# videobrick_alpha4.net
KiCad netlist of a schematic drawn in EAGLE
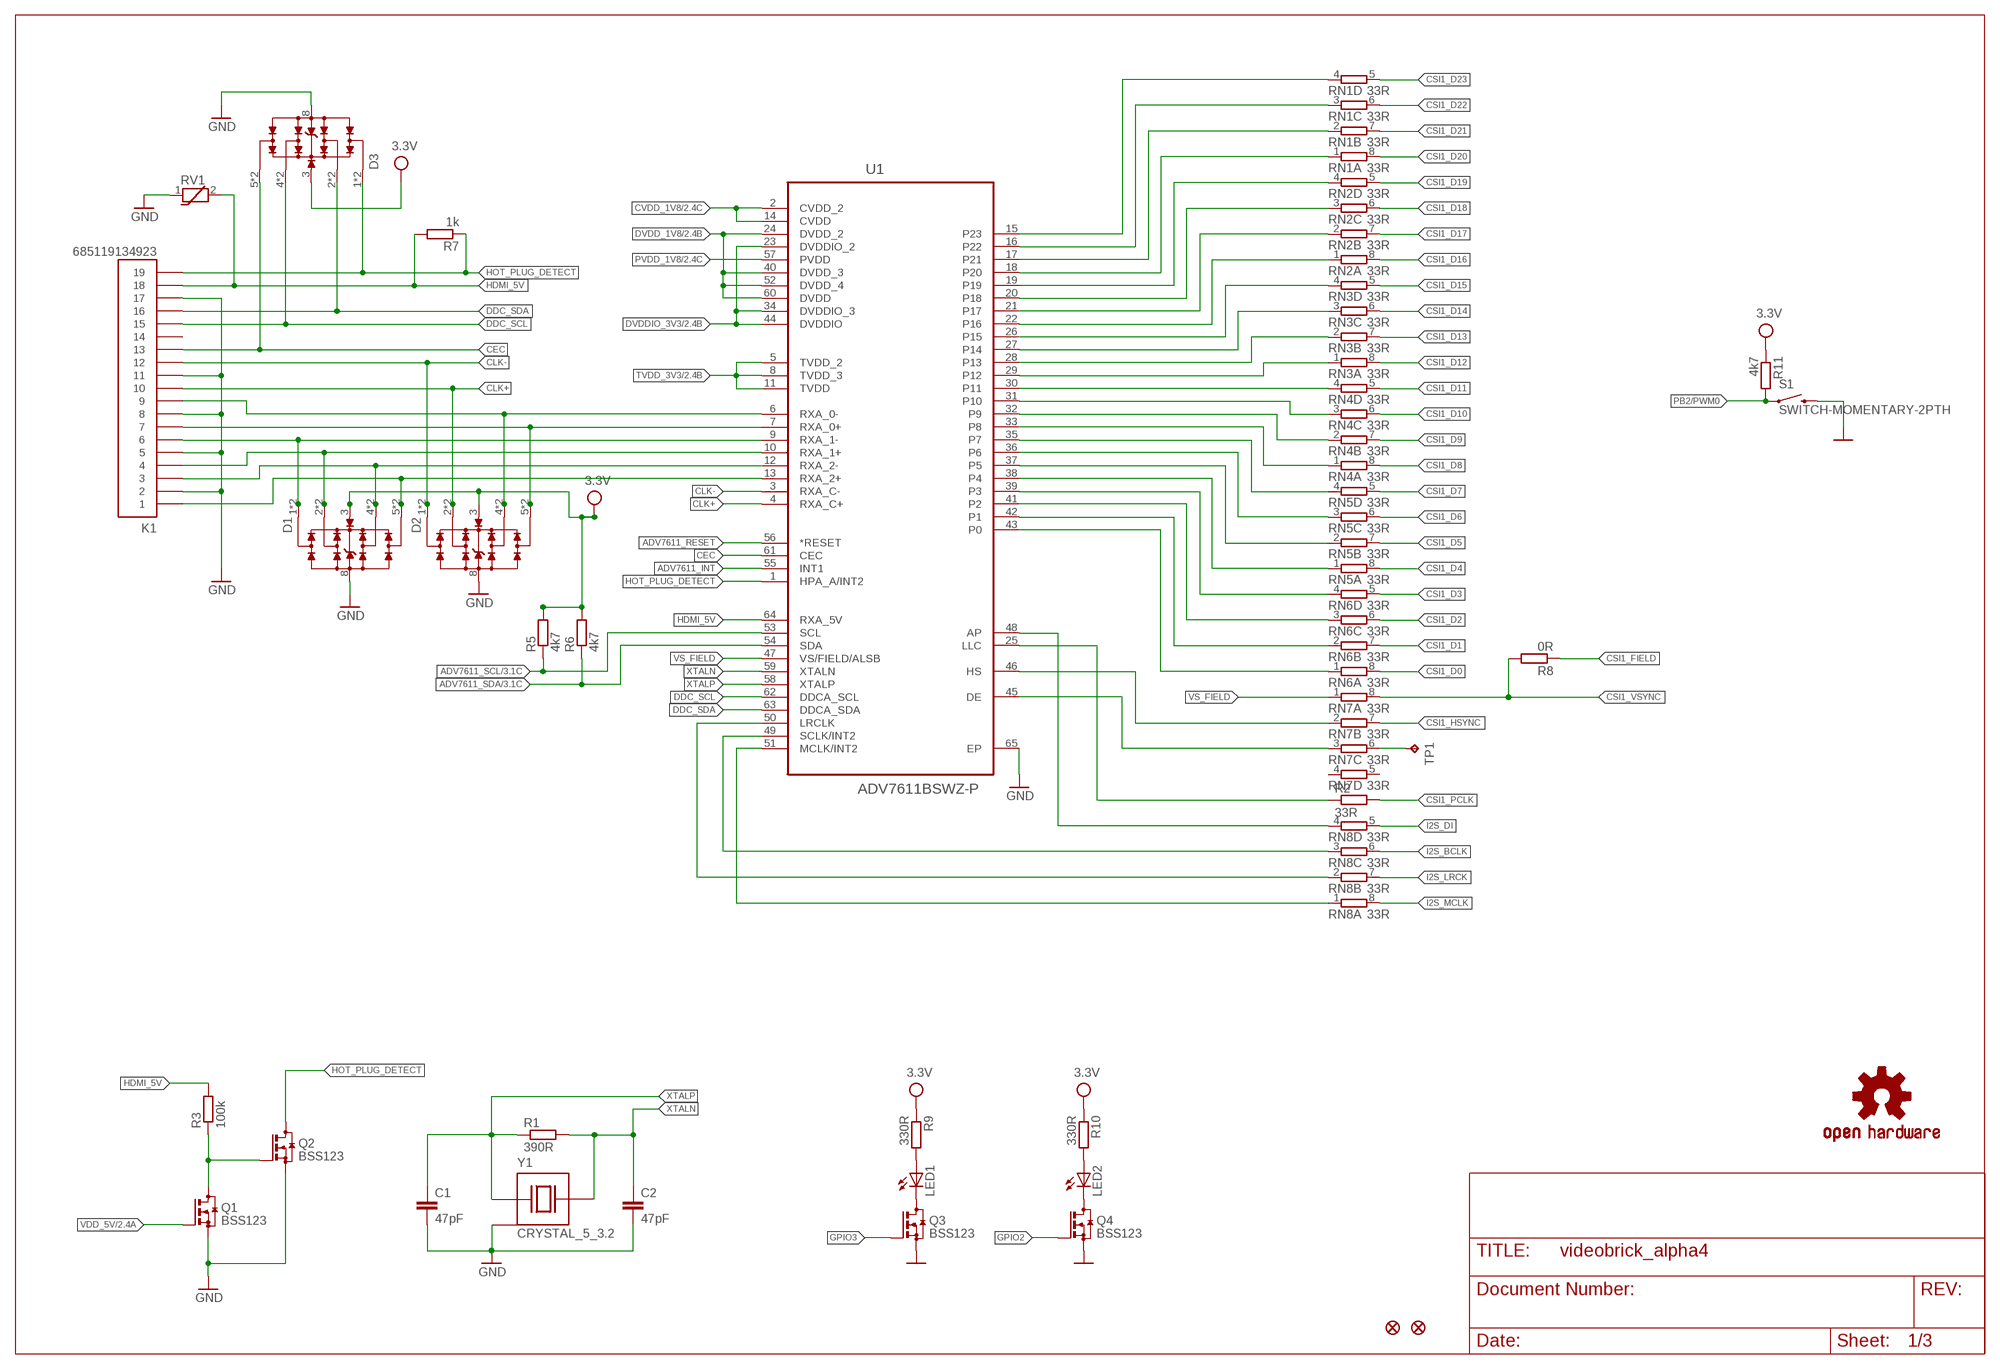
[diagram p0: schematic, sheet 1]
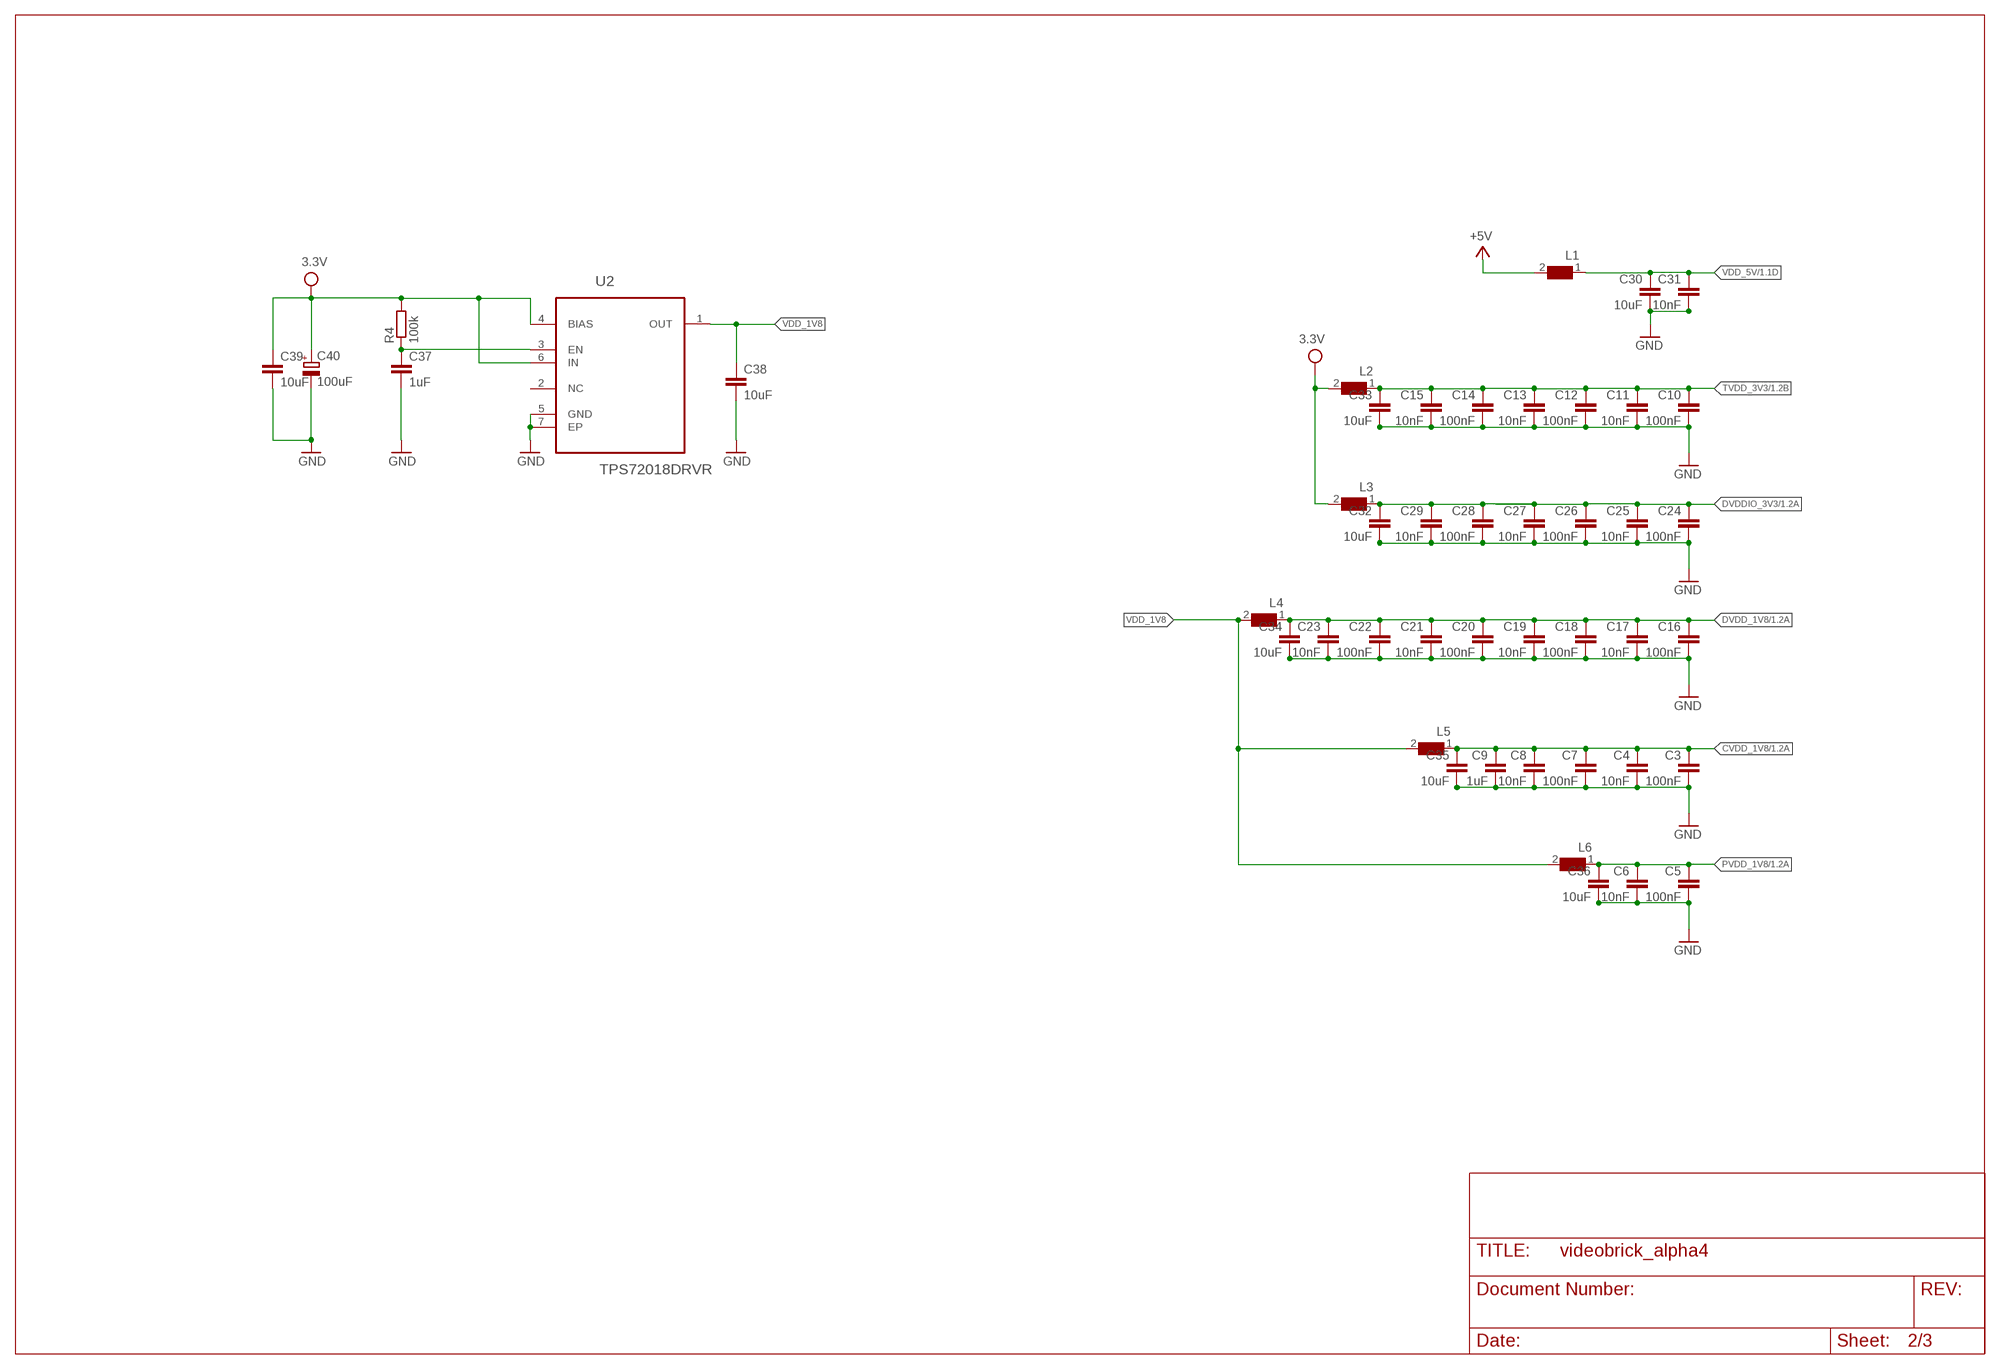
[diagram p1: schematic, sheet 2]
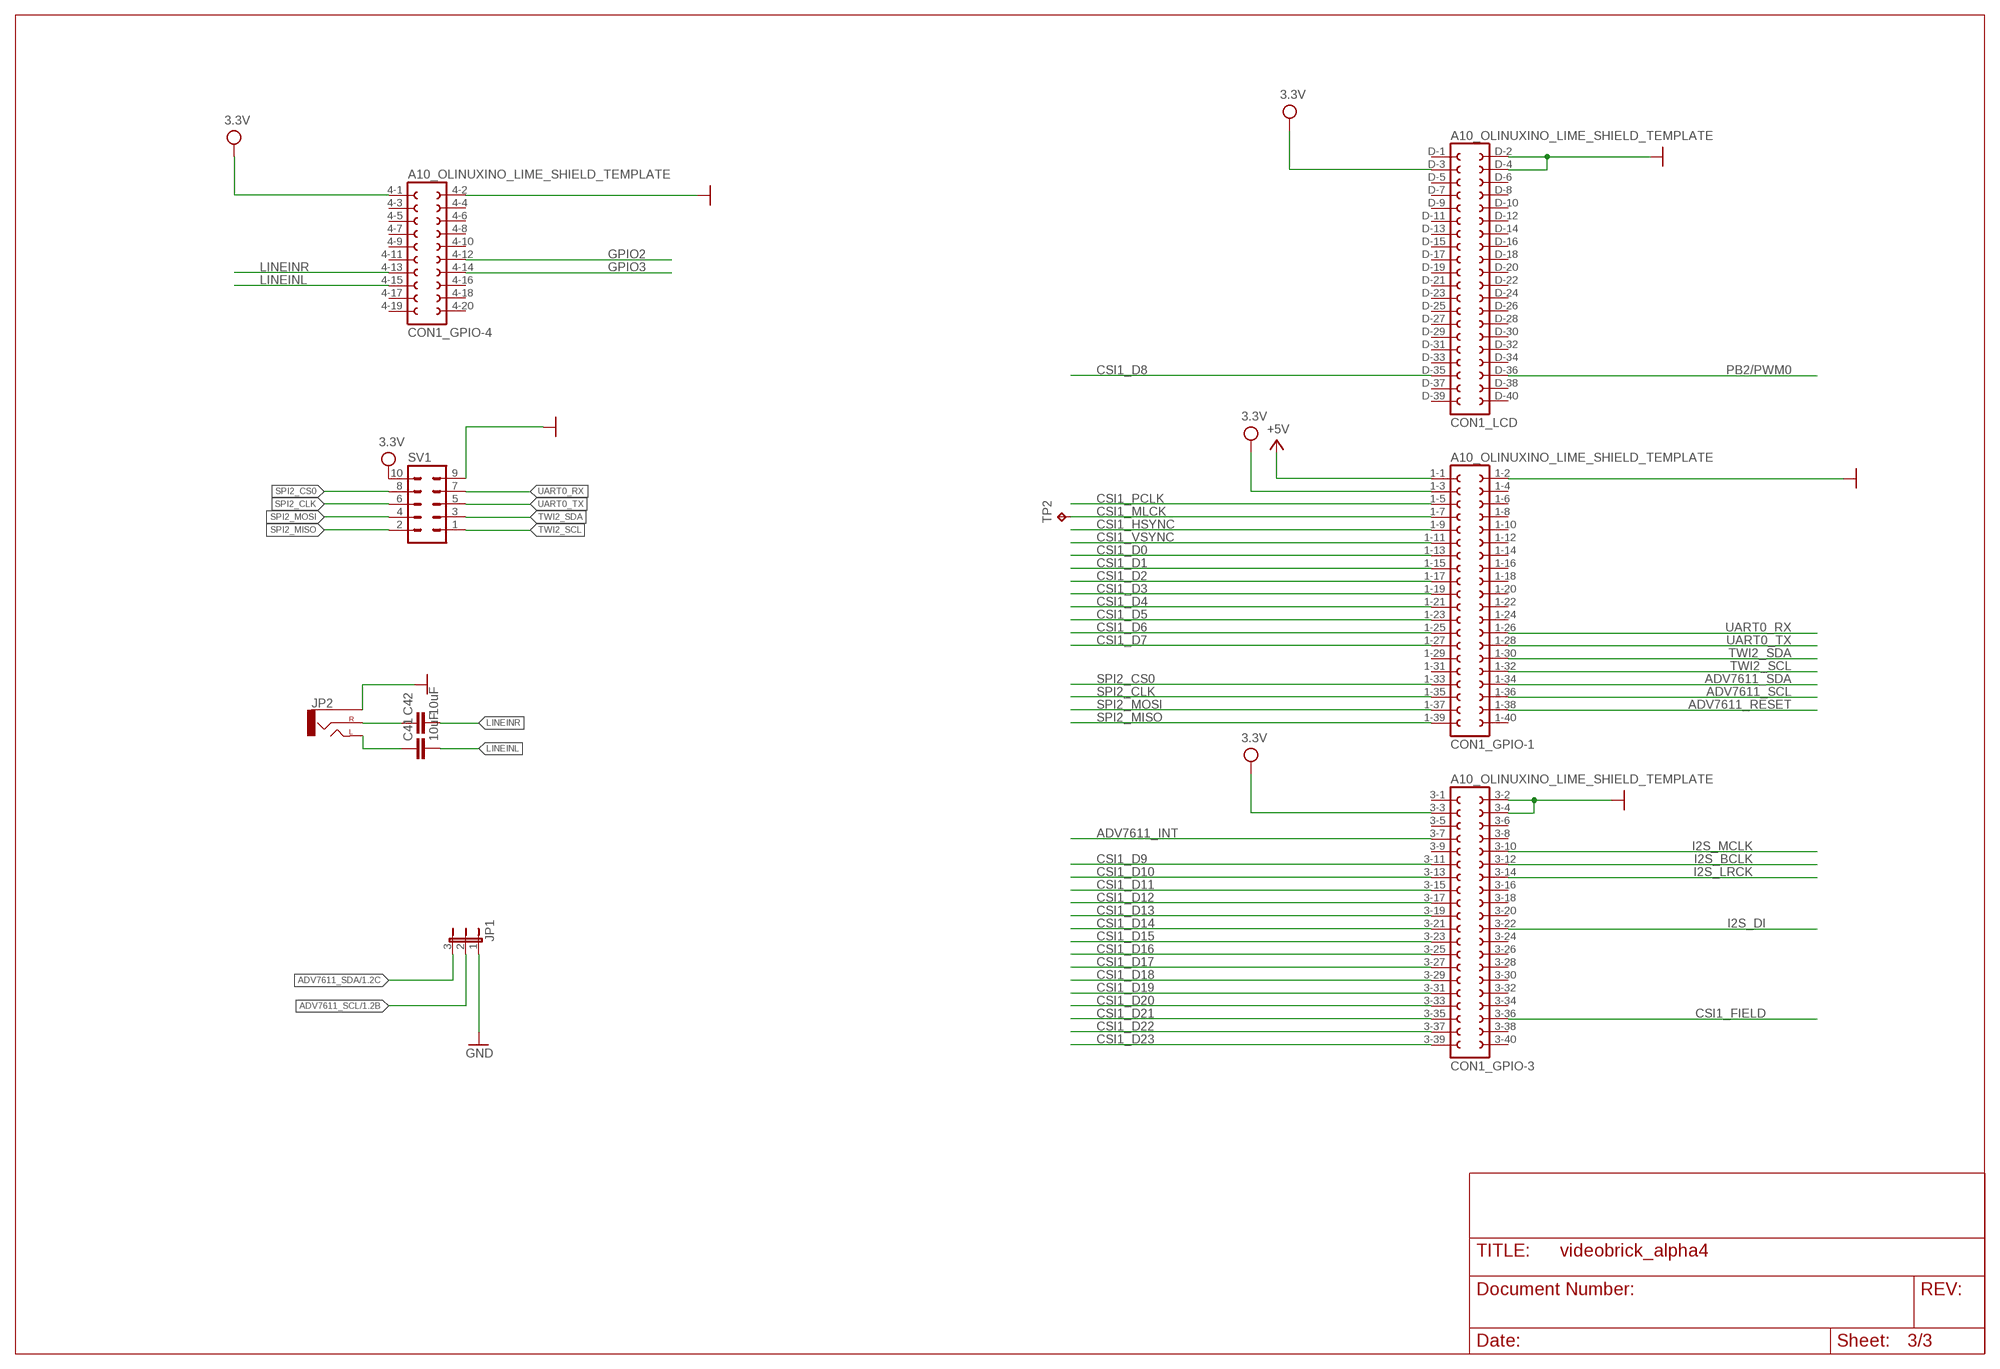
[diagram p2: schematic, sheet 3]

(export (version "E")
  (design (tool "Eeschema 10.0.6"))
  (components
    (comp (ref "C1")
      (value "47pF")
      (footprint "eagle-import:C0402")
      (libsource (lib "eagle-import") (part "C-EUC0402"))
    )
    (comp (ref "C2")
      (value "47pF")
      (footprint "eagle-import:C0402")
      (libsource (lib "eagle-import") (part "C-EUC0402"))
    )
    (comp (ref "D1")
      (value "WE-TVS_82401444")
      (footprint "eagle-import:WE-TVS_MSOP-10L")
      (fields (field (name "MPN") "82401444"))
      (libsource (lib "eagle-import") (part "WE-TVS_82401444"))
    )
    (comp (ref "D2")
      (value "WE-TVS_82401444")
      (footprint "eagle-import:WE-TVS_MSOP-10L")
      (fields (field (name "MPN") "82401444"))
      (libsource (lib "eagle-import") (part "WE-TVS_82401444"))
    )
    (comp (ref "D3")
      (value "WE-TVS_82401444")
      (footprint "eagle-import:WE-TVS_MSOP-10L")
      (fields (field (name "MPN") "82401444"))
      (libsource (lib "eagle-import") (part "WE-TVS_82401444"))
    )
    (comp (ref "FID1")
      (value "FIDUCIALUFIDUCIAL")
      (footprint "eagle-import:MICRO-FIDUCIAL")
      (libsource (lib "eagle-import") (part "FIDUCIALUFIDUCIAL"))
    )
    (comp (ref "FID2")
      (value "FIDUCIAL1X2")
      (footprint "eagle-import:FIDUCIAL-1X2")
      (libsource (lib "eagle-import") (part "FIDUCIAL1X2"))
    )
    (comp (ref "K1")
      (value "685119134923")
      (footprint "eagle-import:685119134923")
      (libsource (lib "eagle-import") (part "685119134923"))
    )
    (comp (ref "LED1")
      (value "LEDCHIPLED_0805")
      (footprint "eagle-import:CHIPLED_0805")
      (libsource (lib "eagle-import") (part "LEDCHIPLED_0805"))
    )
    (comp (ref "LED2")
      (value "LEDCHIPLED_0805")
      (footprint "eagle-import:CHIPLED_0805")
      (libsource (lib "eagle-import") (part "LEDCHIPLED_0805"))
    )
    (comp (ref "LOGO1")
      (value "OSHW-LOGOL")
      (footprint "eagle-import:OSHW-LOGO-L")
      (libsource (lib "eagle-import") (part "OSHW-LOGOL"))
    )
    (comp (ref "Q1")
      (value "BSS123")
      (footprint "eagle-import:SOT23")
      (libsource (lib "eagle-import") (part "BSS123"))
    )
    (comp (ref "Q2")
      (value "BSS123")
      (footprint "eagle-import:SOT23")
      (libsource (lib "eagle-import") (part "BSS123"))
    )
    (comp (ref "Q3")
      (value "BSS123")
      (footprint "eagle-import:SOT23")
      (libsource (lib "eagle-import") (part "BSS123"))
    )
    (comp (ref "Q4")
      (value "BSS123")
      (footprint "eagle-import:SOT23")
      (libsource (lib "eagle-import") (part "BSS123"))
    )
    (comp (ref "R1")
      (value "390R")
      (footprint "eagle-import:R0402")
      (libsource (lib "eagle-import") (part "R-EU_R0402"))
    )
    (comp (ref "R2")
      (value "33R")
      (footprint "eagle-import:R0402")
      (libsource (lib "eagle-import") (part "R-EU_R0402"))
    )
    (comp (ref "R3")
      (value "100k")
      (footprint "eagle-import:R0402")
      (libsource (lib "eagle-import") (part "R-EU_R0402"))
    )
    (comp (ref "R5")
      (value "4k7")
      (footprint "eagle-import:R0402")
      (libsource (lib "eagle-import") (part "R-EU_R0402"))
    )
    (comp (ref "R6")
      (value "4k7")
      (footprint "eagle-import:R0402")
      (libsource (lib "eagle-import") (part "R-EU_R0402"))
    )
    (comp (ref "R7")
      (value "1k")
      (footprint "eagle-import:R0402")
      (libsource (lib "eagle-import") (part "R-EU_R0402"))
    )
    (comp (ref "R8")
      (value "0R")
      (footprint "eagle-import:R0402")
      (libsource (lib "eagle-import") (part "R-EU_R0402"))
    )
    (comp (ref "R9")
      (value "330R")
      (footprint "eagle-import:R0402")
      (libsource (lib "eagle-import") (part "R-EU_R0402"))
    )
    (comp (ref "R10")
      (value "330R")
      (footprint "eagle-import:R0402")
      (libsource (lib "eagle-import") (part "R-EU_R0402"))
    )
    (comp (ref "R11")
      (value "4k7")
      (footprint "eagle-import:R0402")
      (libsource (lib "eagle-import") (part "R-EU_R0402"))
    )
    (comp (ref "RN1")
      (value "33R")
      (footprint "eagle-import:4X0402ARV341")
      (libsource (lib "eagle-import") (part "4R-N0402ARV341"))
    )
    (comp (ref "RN2")
      (value "33R")
      (footprint "eagle-import:4X0402ARV341")
      (libsource (lib "eagle-import") (part "4R-N0402ARV341"))
    )
    (comp (ref "RN3")
      (value "33R")
      (footprint "eagle-import:4X0402ARV341")
      (libsource (lib "eagle-import") (part "4R-N0402ARV341"))
    )
    (comp (ref "RN4")
      (value "33R")
      (footprint "eagle-import:4X0402ARV341")
      (libsource (lib "eagle-import") (part "4R-N0402ARV341"))
    )
    (comp (ref "RN5")
      (value "33R")
      (footprint "eagle-import:4X0402ARV341")
      (libsource (lib "eagle-import") (part "4R-N0402ARV341"))
    )
    (comp (ref "RN6")
      (value "33R")
      (footprint "eagle-import:4X0402ARV341")
      (libsource (lib "eagle-import") (part "4R-N0402ARV341"))
    )
    (comp (ref "RN7")
      (value "33R")
      (footprint "eagle-import:4X0402ARV341")
      (libsource (lib "eagle-import") (part "4R-N0402ARV341"))
    )
    (comp (ref "RN8")
      (value "33R")
      (footprint "eagle-import:4X0402ARV341")
      (libsource (lib "eagle-import") (part "4R-N0402ARV341"))
    )
    (comp (ref "RV1")
      (value "WE-VS-82537040_0402")
      (footprint "eagle-import:WESURGE_0402")
      (fields (field (name "MPN") "82537040"))
      (libsource (lib "eagle-import") (part "WE-VS_0402-82537040"))
    )
    (comp (ref "S1")
      (value "SWITCH-MOMENTARY-2PTH")
      (footprint "eagle-import:TACTILE-PTH")
      (libsource (lib "eagle-import") (part "SWITCH-MOMENTARY-2PTH"))
    )
    (comp (ref "TP1")
      (value "TPTP06R")
      (footprint "eagle-import:TP06R")
      (libsource (lib "eagle-import") (part "TPTP06R"))
    )
    (comp (ref "U1")
      (value "ADV7611BSWZ-P")
      (footprint "eagle-import:QFP50P1200X1200X160-65N")
      (libsource (lib "eagle-import") (part "ADV7611BSWZ-P"))
    )
    (comp (ref "Y1")
      (value "CRYSTAL_5_3.2")
      (footprint "eagle-import:5MM_3.2MM")
      (libsource (lib "eagle-import") (part "CRYSTAL_5_3.2"))
    )
    (comp (ref "C41")
      (value "10uF")
      (footprint "eagle-import:C0805")
      (libsource (lib "eagle-import") (part "C-EUC0805"))
    )
    (comp (ref "C42")
      (value "10uF")
      (footprint "eagle-import:C0805")
      (libsource (lib "eagle-import") (part "C-EUC0805"))
    )
    (comp (ref "CON1")
      (value "A10_OLINUXINO_LIME_SHIELD_TEMPLATE")
      (footprint "eagle-import:A10_OLINUXINO_LIME_SHIELD")
      (libsource (lib "eagle-import") (part "A10_OLINUXINO_LIME_SHIELD_TEMPLATE"))
    )
    (comp (ref "JP1")
      (value "JP2E")
      (footprint "eagle-import:JP2")
      (libsource (lib "eagle-import") (part "JP2E"))
    )
    (comp (ref "JP2")
      (value "AUDIO-JACKPTH")
      (footprint "eagle-import:AUDIO-JACK")
      (libsource (lib "eagle-import") (part "AUDIO-JACKPTH"))
    )
    (comp (ref "SV1")
      (value "MA05-2")
      (footprint "eagle-import:MA05-2")
      (libsource (lib "eagle-import") (part "MA05-2"))
    )
    (comp (ref "TP2")
      (value "TPTP06R")
      (footprint "eagle-import:TP06R")
      (libsource (lib "eagle-import") (part "TPTP06R"))
    )
    (comp (ref "C3")
      (value "100nF")
      (footprint "eagle-import:C0402")
      (libsource (lib "eagle-import") (part "C-EUC0402"))
    )
    (comp (ref "C4")
      (value "10nF")
      (footprint "eagle-import:C0402")
      (libsource (lib "eagle-import") (part "C-EUC0402"))
    )
    (comp (ref "C5")
      (value "100nF")
      (footprint "eagle-import:C0402")
      (libsource (lib "eagle-import") (part "C-EUC0402"))
    )
    (comp (ref "C6")
      (value "10nF")
      (footprint "eagle-import:C0402")
      (libsource (lib "eagle-import") (part "C-EUC0402"))
    )
    (comp (ref "C7")
      (value "100nF")
      (footprint "eagle-import:C0402")
      (libsource (lib "eagle-import") (part "C-EUC0402"))
    )
    (comp (ref "C8")
      (value "10nF")
      (footprint "eagle-import:C0402")
      (libsource (lib "eagle-import") (part "C-EUC0402"))
    )
    (comp (ref "C9")
      (value "1uF")
      (footprint "eagle-import:C0603")
      (libsource (lib "eagle-import") (part "C-EUC0603"))
    )
    (comp (ref "C10")
      (value "100nF")
      (footprint "eagle-import:C0402")
      (libsource (lib "eagle-import") (part "C-EUC0402"))
    )
    (comp (ref "C11")
      (value "10nF")
      (footprint "eagle-import:C0402")
      (libsource (lib "eagle-import") (part "C-EUC0402"))
    )
    (comp (ref "C12")
      (value "100nF")
      (footprint "eagle-import:C0402")
      (libsource (lib "eagle-import") (part "C-EUC0402"))
    )
    (comp (ref "C13")
      (value "10nF")
      (footprint "eagle-import:C0402")
      (libsource (lib "eagle-import") (part "C-EUC0402"))
    )
    (comp (ref "C14")
      (value "100nF")
      (footprint "eagle-import:C0402")
      (libsource (lib "eagle-import") (part "C-EUC0402"))
    )
    (comp (ref "C15")
      (value "10nF")
      (footprint "eagle-import:C0402")
      (libsource (lib "eagle-import") (part "C-EUC0402"))
    )
    (comp (ref "C16")
      (value "100nF")
      (footprint "eagle-import:C0402")
      (libsource (lib "eagle-import") (part "C-EUC0402"))
    )
    (comp (ref "C17")
      (value "10nF")
      (footprint "eagle-import:C0402")
      (libsource (lib "eagle-import") (part "C-EUC0402"))
    )
    (comp (ref "C18")
      (value "100nF")
      (footprint "eagle-import:C0402")
      (libsource (lib "eagle-import") (part "C-EUC0402"))
    )
    (comp (ref "C19")
      (value "10nF")
      (footprint "eagle-import:C0402")
      (libsource (lib "eagle-import") (part "C-EUC0402"))
    )
    (comp (ref "C20")
      (value "100nF")
      (footprint "eagle-import:C0402")
      (libsource (lib "eagle-import") (part "C-EUC0402"))
    )
    (comp (ref "C21")
      (value "10nF")
      (footprint "eagle-import:C0402")
      (libsource (lib "eagle-import") (part "C-EUC0402"))
    )
    (comp (ref "C22")
      (value "100nF")
      (footprint "eagle-import:C0402")
      (libsource (lib "eagle-import") (part "C-EUC0402"))
    )
    (comp (ref "C23")
      (value "10nF")
      (footprint "eagle-import:C0402")
      (libsource (lib "eagle-import") (part "C-EUC0402"))
    )
    (comp (ref "C24")
      (value "100nF")
      (footprint "eagle-import:C0402")
      (libsource (lib "eagle-import") (part "C-EUC0402"))
    )
    (comp (ref "C25")
      (value "10nF")
      (footprint "eagle-import:C0402")
      (libsource (lib "eagle-import") (part "C-EUC0402"))
    )
    (comp (ref "C26")
      (value "100nF")
      (footprint "eagle-import:C0402")
      (libsource (lib "eagle-import") (part "C-EUC0402"))
    )
    (comp (ref "C27")
      (value "10nF")
      (footprint "eagle-import:C0402")
      (libsource (lib "eagle-import") (part "C-EUC0402"))
    )
    (comp (ref "C28")
      (value "100nF")
      (footprint "eagle-import:C0402")
      (libsource (lib "eagle-import") (part "C-EUC0402"))
    )
    (comp (ref "C29")
      (value "10nF")
      (footprint "eagle-import:C0402")
      (libsource (lib "eagle-import") (part "C-EUC0402"))
    )
    (comp (ref "C30")
      (value "10uF")
      (footprint "eagle-import:C0805")
      (libsource (lib "eagle-import") (part "C-EUC0805"))
    )
    (comp (ref "C31")
      (value "10nF")
      (footprint "eagle-import:C0402")
      (libsource (lib "eagle-import") (part "C-EUC0402"))
    )
    (comp (ref "C32")
      (value "10uF")
      (footprint "eagle-import:C0805")
      (libsource (lib "eagle-import") (part "C-EUC0805"))
    )
    (comp (ref "C33")
      (value "10uF")
      (footprint "eagle-import:C0805")
      (libsource (lib "eagle-import") (part "C-EUC0805"))
    )
    (comp (ref "C34")
      (value "10uF")
      (footprint "eagle-import:C0805")
      (libsource (lib "eagle-import") (part "C-EUC0805"))
    )
    (comp (ref "C35")
      (value "10uF")
      (footprint "eagle-import:C0805")
      (libsource (lib "eagle-import") (part "C-EUC0805"))
    )
    (comp (ref "C36")
      (value "10uF")
      (footprint "eagle-import:C0805")
      (libsource (lib "eagle-import") (part "C-EUC0805"))
    )
    (comp (ref "C37")
      (value "1uF")
      (footprint "eagle-import:C0603")
      (libsource (lib "eagle-import") (part "C-EUC0603"))
    )
    (comp (ref "C38")
      (value "10uF")
      (footprint "eagle-import:C0805")
      (libsource (lib "eagle-import") (part "C-EUC0805"))
    )
    (comp (ref "C39")
      (value "10uF")
      (footprint "eagle-import:C0805")
      (libsource (lib "eagle-import") (part "C-EUC0805"))
    )
    (comp (ref "C40")
      (value "100uF")
      (footprint "eagle-import:153CLV-0405")
      (libsource (lib "eagle-import") (part "CPOL-EU153CLV-0405"))
    )
    (comp (ref "L1")
      (value "WE-CBF-742792040_0805")
      (footprint "eagle-import:0805")
      (fields (field (name "MPN") "742792040"))
      (libsource (lib "eagle-import") (part "WE-CBF_0805-742792040"))
    )
    (comp (ref "L2")
      (value "WE-CBF-742792040_0805")
      (footprint "eagle-import:0805")
      (fields (field (name "MPN") "742792040"))
      (libsource (lib "eagle-import") (part "WE-CBF_0805-742792040"))
    )
    (comp (ref "L3")
      (value "WE-CBF-742792040_0805")
      (footprint "eagle-import:0805")
      (fields (field (name "MPN") "742792040"))
      (libsource (lib "eagle-import") (part "WE-CBF_0805-742792040"))
    )
    (comp (ref "L4")
      (value "WE-CBF-742792040_0805")
      (footprint "eagle-import:0805")
      (fields (field (name "MPN") "742792040"))
      (libsource (lib "eagle-import") (part "WE-CBF_0805-742792040"))
    )
    (comp (ref "L5")
      (value "WE-CBF-742792040_0805")
      (footprint "eagle-import:0805")
      (fields (field (name "MPN") "742792040"))
      (libsource (lib "eagle-import") (part "WE-CBF_0805-742792040"))
    )
    (comp (ref "L6")
      (value "WE-CBF-742792040_0805")
      (footprint "eagle-import:0805")
      (fields (field (name "MPN") "742792040"))
      (libsource (lib "eagle-import") (part "WE-CBF_0805-742792040"))
    )
    (comp (ref "R4")
      (value "100k")
      (footprint "eagle-import:R0402")
      (libsource (lib "eagle-import") (part "R-EU_R0402"))
    )
    (comp (ref "U2")
      (value "TPS72018DRVR")
      (footprint "eagle-import:SON65P200X200X80-7N")
      (libsource (lib "eagle-import") (part "TPS72018DRVR"))
    )
  )
  (nets
    (net (code "1") (name "+5V") (class "Default")
      (node (ref "CON1") (pin "1-1") (pinfunction "1_1-1") (pintype "passive"))
      (node (ref "L1") (pin "2") (pinfunction "2_2") (pintype "passive"))
    )
    (net (code "2") (name "ADV7611_INT") (class "Default")
      (node (ref "CON1") (pin "3-7") (pinfunction "7_3-7") (pintype "passive"))
      (node (ref "U1") (pin "55") (pinfunction "INT1_55") (pintype "input"))
    )
    (net (code "3") (name "ADV7611_RESET") (class "Default")
      (node (ref "CON1") (pin "1-38") (pinfunction "38_1-38") (pintype "passive"))
      (node (ref "U1") (pin "56") (pinfunction "*RESET_56") (pintype "input"))
    )
    (net (code "4") (name "ADV7611_SCL") (class "Default")
      (node (ref "CON1") (pin "1-36") (pinfunction "36_1-36") (pintype "passive"))
      (node (ref "JP1") (pin "2") (pinfunction "2_2") (pintype "passive"))
      (node (ref "R5") (pin "1") (pinfunction "1_1") (pintype "passive"))
      (node (ref "U1") (pin "53") (pinfunction "SCL_53") (pintype "input"))
    )
    (net (code "5") (name "ADV7611_SDA") (class "Default")
      (node (ref "CON1") (pin "1-34") (pinfunction "34_1-34") (pintype "passive"))
      (node (ref "JP1") (pin "3") (pinfunction "3_3") (pintype "passive"))
      (node (ref "R6") (pin "1") (pinfunction "1_1") (pintype "passive"))
      (node (ref "U1") (pin "54") (pinfunction "SDA_54") (pintype "bidirectional"))
    )
    (net (code "6") (name "CEC") (class "Default")
      (node (ref "D3") (pin "5") (pinfunction "4_5") (pintype "passive"))
      (node (ref "D3") (pin "6") (pinfunction "4_6") (pintype "passive"))
      (node (ref "K1") (pin "13") (pinfunction "13_13") (pintype "passive"))
      (node (ref "U1") (pin "61") (pinfunction "CEC_61") (pintype "input"))
    )
    (net (code "7") (name "CLK+") (class "Default")
      (node (ref "D2") (pin "2") (pinfunction "2_2") (pintype "passive"))
      (node (ref "D2") (pin "9") (pinfunction "2_9") (pintype "passive"))
      (node (ref "K1") (pin "10") (pinfunction "10_10") (pintype "passive"))
      (node (ref "U1") (pin "4") (pinfunction "RXA_C+_4") (pintype "input"))
    )
    (net (code "8") (name "CLK-") (class "Default")
      (node (ref "D2") (pin "1") (pinfunction "1_1") (pintype "passive"))
      (node (ref "D2") (pin "10") (pinfunction "1_10") (pintype "passive"))
      (node (ref "K1") (pin "12") (pinfunction "12_12") (pintype "passive"))
      (node (ref "U1") (pin "3") (pinfunction "RXA_C-_3") (pintype "input"))
    )
    (net (code "9") (name "CSI1_D0") (class "Default")
      (node (ref "CON1") (pin "1-13") (pinfunction "13_1-13") (pintype "passive"))
      (node (ref "RN6") (pin "8") (pinfunction "2_8") (pintype "passive"))
    )
    (net (code "10") (name "CSI1_D1") (class "Default")
      (node (ref "CON1") (pin "1-15") (pinfunction "15_1-15") (pintype "passive"))
      (node (ref "RN6") (pin "7") (pinfunction "2_7") (pintype "passive"))
    )
    (net (code "11") (name "CSI1_D2") (class "Default")
      (node (ref "CON1") (pin "1-17") (pinfunction "17_1-17") (pintype "passive"))
      (node (ref "RN6") (pin "6") (pinfunction "2_6") (pintype "passive"))
    )
    (net (code "12") (name "CSI1_D3") (class "Default")
      (node (ref "CON1") (pin "1-19") (pinfunction "19_1-19") (pintype "passive"))
      (node (ref "RN6") (pin "5") (pinfunction "2_5") (pintype "passive"))
    )
    (net (code "13") (name "CSI1_D4") (class "Default")
      (node (ref "CON1") (pin "1-21") (pinfunction "21_1-21") (pintype "passive"))
      (node (ref "RN5") (pin "8") (pinfunction "2_8") (pintype "passive"))
    )
    (net (code "14") (name "CSI1_D5") (class "Default")
      (node (ref "CON1") (pin "1-23") (pinfunction "23_1-23") (pintype "passive"))
      (node (ref "RN5") (pin "7") (pinfunction "2_7") (pintype "passive"))
    )
    (net (code "15") (name "CSI1_D6") (class "Default")
      (node (ref "CON1") (pin "1-25") (pinfunction "25_1-25") (pintype "passive"))
      (node (ref "RN5") (pin "6") (pinfunction "2_6") (pintype "passive"))
    )
    (net (code "16") (name "CSI1_D7") (class "Default")
      (node (ref "CON1") (pin "1-27") (pinfunction "27_1-27") (pintype "passive"))
      (node (ref "RN5") (pin "5") (pinfunction "2_5") (pintype "passive"))
    )
    (net (code "17") (name "CSI1_D8") (class "Default")
      (node (ref "CON1") (pin "D-35") (pinfunction "35_D-35") (pintype "passive"))
      (node (ref "RN4") (pin "8") (pinfunction "2_8") (pintype "passive"))
    )
    (net (code "18") (name "CSI1_D9") (class "Default")
      (node (ref "CON1") (pin "3-11") (pinfunction "11_3-11") (pintype "passive"))
      (node (ref "RN4") (pin "7") (pinfunction "2_7") (pintype "passive"))
    )
    (net (code "19") (name "CSI1_D10") (class "Default")
      (node (ref "CON1") (pin "3-13") (pinfunction "13_3-13") (pintype "passive"))
      (node (ref "RN4") (pin "6") (pinfunction "2_6") (pintype "passive"))
    )
    (net (code "20") (name "CSI1_D11") (class "Default")
      (node (ref "CON1") (pin "3-15") (pinfunction "15_3-15") (pintype "passive"))
      (node (ref "RN4") (pin "5") (pinfunction "2_5") (pintype "passive"))
    )
    (net (code "21") (name "CSI1_D12") (class "Default")
      (node (ref "CON1") (pin "3-17") (pinfunction "17_3-17") (pintype "passive"))
      (node (ref "RN3") (pin "8") (pinfunction "2_8") (pintype "passive"))
    )
    (net (code "22") (name "CSI1_D13") (class "Default")
      (node (ref "CON1") (pin "3-19") (pinfunction "19_3-19") (pintype "passive"))
      (node (ref "RN3") (pin "7") (pinfunction "2_7") (pintype "passive"))
    )
    (net (code "23") (name "CSI1_D14") (class "Default")
      (node (ref "CON1") (pin "3-21") (pinfunction "21_3-21") (pintype "passive"))
      (node (ref "RN3") (pin "6") (pinfunction "2_6") (pintype "passive"))
    )
    (net (code "24") (name "CSI1_D15") (class "Default")
      (node (ref "CON1") (pin "3-23") (pinfunction "23_3-23") (pintype "passive"))
      (node (ref "RN3") (pin "5") (pinfunction "2_5") (pintype "passive"))
    )
    (net (code "25") (name "CSI1_D16") (class "Default")
      (node (ref "CON1") (pin "3-25") (pinfunction "25_3-25") (pintype "passive"))
      (node (ref "RN2") (pin "8") (pinfunction "2_8") (pintype "passive"))
    )
    (net (code "26") (name "CSI1_D17") (class "Default")
      (node (ref "CON1") (pin "3-27") (pinfunction "27_3-27") (pintype "passive"))
      (node (ref "RN2") (pin "7") (pinfunction "2_7") (pintype "passive"))
    )
    (net (code "27") (name "CSI1_D18") (class "Default")
      (node (ref "CON1") (pin "3-29") (pinfunction "29_3-29") (pintype "passive"))
      (node (ref "RN2") (pin "6") (pinfunction "2_6") (pintype "passive"))
    )
    (net (code "28") (name "CSI1_D19") (class "Default")
      (node (ref "CON1") (pin "3-31") (pinfunction "31_3-31") (pintype "passive"))
      (node (ref "RN2") (pin "5") (pinfunction "2_5") (pintype "passive"))
    )
    (net (code "29") (name "CSI1_D20") (class "Default")
      (node (ref "CON1") (pin "3-33") (pinfunction "33_3-33") (pintype "passive"))
      (node (ref "RN1") (pin "8") (pinfunction "2_8") (pintype "passive"))
    )
    (net (code "30") (name "CSI1_D21") (class "Default")
      (node (ref "CON1") (pin "3-35") (pinfunction "35_3-35") (pintype "passive"))
      (node (ref "RN1") (pin "7") (pinfunction "2_7") (pintype "passive"))
    )
    (net (code "31") (name "CSI1_D22") (class "Default")
      (node (ref "CON1") (pin "3-37") (pinfunction "37_3-37") (pintype "passive"))
      (node (ref "RN1") (pin "6") (pinfunction "2_6") (pintype "passive"))
    )
    (net (code "32") (name "CSI1_D23") (class "Default")
      (node (ref "CON1") (pin "3-39") (pinfunction "39_3-39") (pintype "passive"))
      (node (ref "RN1") (pin "5") (pinfunction "2_5") (pintype "passive"))
    )
    (net (code "33") (name "CSI1_FIELD") (class "Default")
      (node (ref "CON1") (pin "3-36") (pinfunction "36_3-36") (pintype "passive"))
      (node (ref "R8") (pin "1") (pinfunction "1_1") (pintype "passive"))
    )
    (net (code "34") (name "CSI1_HSYNC") (class "Default")
      (node (ref "CON1") (pin "1-9") (pinfunction "9_1-9") (pintype "passive"))
      (node (ref "RN7") (pin "7") (pinfunction "2_7") (pintype "passive"))
    )
    (net (code "35") (name "CSI1_MLCK") (class "Default")
      (node (ref "CON1") (pin "1-7") (pinfunction "7_1-7") (pintype "passive"))
      (node (ref "TP2") (pin "TP") (pinfunction "TP_TP") (pintype "input"))
    )
    (net (code "36") (name "CSI1_PCLK") (class "Default")
      (node (ref "CON1") (pin "1-5") (pinfunction "5_1-5") (pintype "passive"))
      (node (ref "R2") (pin "2") (pinfunction "2_2") (pintype "passive"))
    )
    (net (code "37") (name "CSI1_VSYNC") (class "Default")
      (node (ref "CON1") (pin "1-11") (pinfunction "11_1-11") (pintype "passive"))
      (node (ref "R8") (pin "2") (pinfunction "2_2") (pintype "passive"))
      (node (ref "RN7") (pin "8") (pinfunction "2_8") (pintype "passive"))
    )
    (net (code "38") (name "CVDD_1V8") (class "Default")
      (node (ref "C3") (pin "1") (pinfunction "1_1") (pintype "passive"))
      (node (ref "C35") (pin "1") (pinfunction "1_1") (pintype "passive"))
      (node (ref "C4") (pin "1") (pinfunction "1_1") (pintype "passive"))
      (node (ref "C7") (pin "1") (pinfunction "1_1") (pintype "passive"))
      (node (ref "C8") (pin "1") (pinfunction "1_1") (pintype "passive"))
      (node (ref "C9") (pin "1") (pinfunction "1_1") (pintype "passive"))
      (node (ref "L5") (pin "1") (pinfunction "1_1") (pintype "passive"))
      (node (ref "U1") (pin "14") (pinfunction "CVDD_14") (pintype "power_in"))
      (node (ref "U1") (pin "2") (pinfunction "CVDD_2_2") (pintype "power_in"))
    )
    (net (code "39") (name "DDC_SCL") (class "Default")
      (node (ref "D3") (pin "4") (pinfunction "3_4") (pintype "passive"))
      (node (ref "D3") (pin "7") (pinfunction "3_7") (pintype "passive"))
      (node (ref "K1") (pin "15") (pinfunction "15_15") (pintype "passive"))
      (node (ref "U1") (pin "62") (pinfunction "DDCA_SCL_62") (pintype "input"))
    )
    (net (code "40") (name "DDC_SDA") (class "Default")
      (node (ref "D3") (pin "2") (pinfunction "2_2") (pintype "passive"))
      (node (ref "D3") (pin "9") (pinfunction "2_9") (pintype "passive"))
      (node (ref "K1") (pin "16") (pinfunction "16_16") (pintype "passive"))
      (node (ref "U1") (pin "63") (pinfunction "DDCA_SDA_63") (pintype "input"))
    )
    (net (code "41") (name "DVDDIO_3V3") (class "Default")
      (node (ref "C24") (pin "1") (pinfunction "1_1") (pintype "passive"))
      (node (ref "C25") (pin "1") (pinfunction "1_1") (pintype "passive"))
      (node (ref "C26") (pin "1") (pinfunction "1_1") (pintype "passive"))
      (node (ref "C27") (pin "1") (pinfunction "1_1") (pintype "passive"))
      (node (ref "C28") (pin "1") (pinfunction "1_1") (pintype "passive"))
      (node (ref "C29") (pin "1") (pinfunction "1_1") (pintype "passive"))
      (node (ref "C32") (pin "1") (pinfunction "1_1") (pintype "passive"))
      (node (ref "L3") (pin "1") (pinfunction "1_1") (pintype "passive"))
      (node (ref "U1") (pin "23") (pinfunction "DVDDIO_2_23") (pintype "power_in"))
      (node (ref "U1") (pin "34") (pinfunction "DVDDIO_3_34") (pintype "power_in"))
      (node (ref "U1") (pin "44") (pinfunction "DVDDIO_44") (pintype "power_in"))
    )
    (net (code "42") (name "DVDD_1V8") (class "Default")
      (node (ref "C16") (pin "1") (pinfunction "1_1") (pintype "passive"))
      (node (ref "C17") (pin "1") (pinfunction "1_1") (pintype "passive"))
      (node (ref "C18") (pin "1") (pinfunction "1_1") (pintype "passive"))
      (node (ref "C19") (pin "1") (pinfunction "1_1") (pintype "passive"))
      (node (ref "C20") (pin "1") (pinfunction "1_1") (pintype "passive"))
      (node (ref "C21") (pin "1") (pinfunction "1_1") (pintype "passive"))
      (node (ref "C22") (pin "1") (pinfunction "1_1") (pintype "passive"))
      (node (ref "C23") (pin "1") (pinfunction "1_1") (pintype "passive"))
      (node (ref "C34") (pin "1") (pinfunction "1_1") (pintype "passive"))
      (node (ref "L4") (pin "1") (pinfunction "1_1") (pintype "passive"))
      (node (ref "U1") (pin "24") (pinfunction "DVDD_2_24") (pintype "power_in"))
      (node (ref "U1") (pin "40") (pinfunction "DVDD_3_40") (pintype "power_in"))
      (node (ref "U1") (pin "52") (pinfunction "DVDD_4_52") (pintype "power_in"))
      (node (ref "U1") (pin "60") (pinfunction "DVDD_60") (pintype "power_in"))
    )
    (net (code "43") (name "GND") (class "Default")
      (node (ref "C1") (pin "2") (pinfunction "2_2") (pintype "passive"))
      (node (ref "C10") (pin "2") (pinfunction "2_2") (pintype "passive"))
      (node (ref "C11") (pin "2") (pinfunction "2_2") (pintype "passive"))
      (node (ref "C12") (pin "2") (pinfunction "2_2") (pintype "passive"))
      (node (ref "C13") (pin "2") (pinfunction "2_2") (pintype "passive"))
      (node (ref "C14") (pin "2") (pinfunction "2_2") (pintype "passive"))
      (node (ref "C15") (pin "2") (pinfunction "2_2") (pintype "passive"))
      (node (ref "C16") (pin "2") (pinfunction "2_2") (pintype "passive"))
      (node (ref "C17") (pin "2") (pinfunction "2_2") (pintype "passive"))
      (node (ref "C18") (pin "2") (pinfunction "2_2") (pintype "passive"))
      (node (ref "C19") (pin "2") (pinfunction "2_2") (pintype "passive"))
      (node (ref "C2") (pin "2") (pinfunction "2_2") (pintype "passive"))
      (node (ref "C20") (pin "2") (pinfunction "2_2") (pintype "passive"))
      (node (ref "C21") (pin "2") (pinfunction "2_2") (pintype "passive"))
      (node (ref "C22") (pin "2") (pinfunction "2_2") (pintype "passive"))
      (node (ref "C23") (pin "2") (pinfunction "2_2") (pintype "passive"))
      (node (ref "C24") (pin "2") (pinfunction "2_2") (pintype "passive"))
      (node (ref "C25") (pin "2") (pinfunction "2_2") (pintype "passive"))
      (node (ref "C26") (pin "2") (pinfunction "2_2") (pintype "passive"))
      (node (ref "C27") (pin "2") (pinfunction "2_2") (pintype "passive"))
      (node (ref "C28") (pin "2") (pinfunction "2_2") (pintype "passive"))
      (node (ref "C29") (pin "2") (pinfunction "2_2") (pintype "passive"))
      (node (ref "C3") (pin "2") (pinfunction "2_2") (pintype "passive"))
      (node (ref "C30") (pin "2") (pinfunction "2_2") (pintype "passive"))
      (node (ref "C31") (pin "2") (pinfunction "2_2") (pintype "passive"))
      (node (ref "C32") (pin "2") (pinfunction "2_2") (pintype "passive"))
      (node (ref "C33") (pin "2") (pinfunction "2_2") (pintype "passive"))
      (node (ref "C34") (pin "2") (pinfunction "2_2") (pintype "passive"))
      (node (ref "C35") (pin "2") (pinfunction "2_2") (pintype "passive"))
      (node (ref "C36") (pin "2") (pinfunction "2_2") (pintype "passive"))
      (node (ref "C37") (pin "2") (pinfunction "2_2") (pintype "passive"))
      (node (ref "C38") (pin "2") (pinfunction "2_2") (pintype "passive"))
      (node (ref "C39") (pin "2") (pinfunction "2_2") (pintype "passive"))
      (node (ref "C4") (pin "2") (pinfunction "2_2") (pintype "passive"))
      (node (ref "C40") (pin "-") (pinfunction "-_-") (pintype "passive"))
      (node (ref "C5") (pin "2") (pinfunction "2_2") (pintype "passive"))
      (node (ref "C6") (pin "2") (pinfunction "2_2") (pintype "passive"))
      (node (ref "C7") (pin "2") (pinfunction "2_2") (pintype "passive"))
      (node (ref "C8") (pin "2") (pinfunction "2_2") (pintype "passive"))
      (node (ref "C9") (pin "2") (pinfunction "2_2") (pintype "passive"))
      (node (ref "CON1") (pin "1-2") (pinfunction "2_1-2") (pintype "passive"))
      (node (ref "CON1") (pin "3-2") (pinfunction "2_3-2") (pintype "passive"))
      (node (ref "CON1") (pin "3-4") (pinfunction "4_3-4") (pintype "passive"))
      (node (ref "CON1") (pin "4-2") (pinfunction "2_4-2") (pintype "passive"))
      (node (ref "CON1") (pin "D-2") (pinfunction "2_D-2") (pintype "passive"))
      (node (ref "CON1") (pin "D-4") (pinfunction "4_D-4") (pintype "passive"))
      (node (ref "D1") (pin "8") (pinfunction "GND_8") (pintype "power_in"))
      (node (ref "D2") (pin "8") (pinfunction "GND_8") (pintype "power_in"))
      (node (ref "D3") (pin "8") (pinfunction "GND_8") (pintype "power_in"))
      (node (ref "JP1") (pin "1") (pinfunction "1_1") (pintype "passive"))
      (node (ref "JP2") (pin "SLEEVE") (pinfunction "SLEEVE_SLEEVE") (pintype "bidirectional"))
      (node (ref "K1") (pin "11") (pinfunction "11_11") (pintype "passive"))
      (node (ref "K1") (pin "17") (pinfunction "17_17") (pintype "passive"))
      (node (ref "K1") (pin "2") (pinfunction "2_2") (pintype "passive"))
      (node (ref "K1") (pin "5") (pinfunction "5_5") (pintype "passive"))
      (node (ref "K1") (pin "8") (pinfunction "8_8") (pintype "passive"))
      (node (ref "Q1") (pin "2") (pinfunction "S_2") (pintype "passive"))
      (node (ref "Q2") (pin "2") (pinfunction "S_2") (pintype "passive"))
      (node (ref "Q3") (pin "2") (pinfunction "S_2") (pintype "passive"))
      (node (ref "Q4") (pin "2") (pinfunction "S_2") (pintype "passive"))
      (node (ref "RV1") (pin "1") (pinfunction "1_1") (pintype "passive"))
      (node (ref "S1") (pin "3") (pinfunction "2_3") (pintype "passive"))
      (node (ref "SV1") (pin "9") (pinfunction "9_9") (pintype "passive"))
      (node (ref "U1") (pin "65") (pinfunction "EP_65") (pintype "passive"))
      (node (ref "U2") (pin "5") (pinfunction "GND_5") (pintype "passive"))
      (node (ref "U2") (pin "7") (pinfunction "EP_7") (pintype "passive"))
      (node (ref "Y1") (pin "P$2") (pinfunction "3_P$2") (pintype "passive"))
      (node (ref "Y1") (pin "P$4#") (pinfunction "3_P$4#") (pintype "passive"))
    )
    (net (code "44") (name "GPIO2") (class "Default")
      (node (ref "CON1") (pin "4-12") (pinfunction "12_4-12") (pintype "passive"))
      (node (ref "Q4") (pin "1") (pinfunction "G_1") (pintype "passive"))
    )
    (net (code "45") (name "GPIO3") (class "Default")
      (node (ref "CON1") (pin "4-14") (pinfunction "14_4-14") (pintype "passive"))
      (node (ref "Q3") (pin "1") (pinfunction "G_1") (pintype "passive"))
    )
    (net (code "46") (name "HDMI_5V") (class "Default")
      (node (ref "K1") (pin "18") (pinfunction "18_18") (pintype "passive"))
      (node (ref "R3") (pin "2") (pinfunction "2_2") (pintype "passive"))
      (node (ref "R7") (pin "2") (pinfunction "2_2") (pintype "passive"))
      (node (ref "RV1") (pin "2") (pinfunction "2_2") (pintype "passive"))
      (node (ref "U1") (pin "64") (pinfunction "RXA_5V_64") (pintype "input"))
    )
    (net (code "47") (name "HOT_PLUG_DETECT") (class "Default")
      (node (ref "D3") (pin "1") (pinfunction "1_1") (pintype "passive"))
      (node (ref "D3") (pin "10") (pinfunction "1_10") (pintype "passive"))
      (node (ref "K1") (pin "19") (pinfunction "19_19") (pintype "passive"))
      (node (ref "Q2") (pin "3") (pinfunction "D_3") (pintype "passive"))
      (node (ref "R7") (pin "1") (pinfunction "1_1") (pintype "passive"))
      (node (ref "U1") (pin "1") (pinfunction "HPA_A/INT2_1") (pintype "input"))
    )
    (net (code "48") (name "I2S_BCLK") (class "Default")
      (node (ref "CON1") (pin "3-12") (pinfunction "12_3-12") (pintype "passive"))
      (node (ref "RN8") (pin "6") (pinfunction "2_6") (pintype "passive"))
    )
    (net (code "49") (name "I2S_DI") (class "Default")
      (node (ref "CON1") (pin "3-22") (pinfunction "22_3-22") (pintype "passive"))
      (node (ref "RN8") (pin "5") (pinfunction "2_5") (pintype "passive"))
    )
    (net (code "50") (name "I2S_LRCK") (class "Default")
      (node (ref "CON1") (pin "3-14") (pinfunction "14_3-14") (pintype "passive"))
      (node (ref "RN8") (pin "7") (pinfunction "2_7") (pintype "passive"))
    )
    (net (code "51") (name "I2S_MCLK") (class "Default")
      (node (ref "CON1") (pin "3-10") (pinfunction "10_3-10") (pintype "passive"))
      (node (ref "RN8") (pin "8") (pinfunction "2_8") (pintype "passive"))
    )
    (net (code "52") (name "LINEINL") (class "Default")
      (node (ref "C41") (pin "2") (pinfunction "2_2") (pintype "passive"))
      (node (ref "CON1") (pin "4-15") (pinfunction "15_4-15") (pintype "passive"))
    )
    (net (code "53") (name "LINEINR") (class "Default")
      (node (ref "C42") (pin "2") (pinfunction "2_2") (pintype "passive"))
      (node (ref "CON1") (pin "4-13") (pinfunction "13_4-13") (pintype "passive"))
    )
    (net (code "54") (name "Net-(JP2-LEFT)") (class "Default")
      (node (ref "C41") (pin "1") (pinfunction "1_1") (pintype "passive"))
      (node (ref "JP2") (pin "TIP") (pinfunction "LEFT_TIP") (pintype "bidirectional"))
    )
    (net (code "55") (name "Net-(JP2-RIGHT)") (class "Default")
      (node (ref "C42") (pin "1") (pinfunction "1_1") (pintype "passive"))
      (node (ref "JP2") (pin "RING") (pinfunction "RIGHT_RING") (pintype "bidirectional"))
    )
    (net (code "56") (name "Net-(LED1-PadA)") (class "Default")
      (node (ref "LED1") (pin "A") (pinfunction "A_A") (pintype "passive"))
      (node (ref "R9") (pin "2") (pinfunction "2_2") (pintype "passive"))
    )
    (net (code "57") (name "Net-(LED2-PadA)") (class "Default")
      (node (ref "LED2") (pin "A") (pinfunction "A_A") (pintype "passive"))
      (node (ref "R10") (pin "2") (pinfunction "2_2") (pintype "passive"))
    )
    (net (code "58") (name "Net-(Q1-D)") (class "Default")
      (node (ref "Q1") (pin "3") (pinfunction "D_3") (pintype "passive"))
      (node (ref "Q2") (pin "1") (pinfunction "G_1") (pintype "passive"))
      (node (ref "R3") (pin "1") (pinfunction "1_1") (pintype "passive"))
    )
    (net (code "59") (name "Net-(Q3-D)") (class "Default")
      (node (ref "LED1") (pin "C") (pinfunction "C_C") (pintype "passive"))
      (node (ref "Q3") (pin "3") (pinfunction "D_3") (pintype "passive"))
    )
    (net (code "60") (name "Net-(Q4-D)") (class "Default")
      (node (ref "LED2") (pin "C") (pinfunction "C_C") (pintype "passive"))
      (node (ref "Q4") (pin "3") (pinfunction "D_3") (pintype "passive"))
    )
    (net (code "61") (name "Net-(RN1B-1)") (class "Default")
      (node (ref "RN1") (pin "2") (pinfunction "1_2") (pintype "passive"))
      (node (ref "U1") (pin "17") (pinfunction "P21_17") (pintype "output"))
    )
    (net (code "62") (name "Net-(RN1C-1)") (class "Default")
      (node (ref "RN1") (pin "3") (pinfunction "1_3") (pintype "passive"))
      (node (ref "U1") (pin "16") (pinfunction "P22_16") (pintype "output"))
    )
    (net (code "63") (name "Net-(RN1D-1)") (class "Default")
      (node (ref "RN1") (pin "4") (pinfunction "1_4") (pintype "passive"))
      (node (ref "U1") (pin "15") (pinfunction "P23_15") (pintype "output"))
    )
    (net (code "64") (name "Net-(RN2B-1)") (class "Default")
      (node (ref "RN2") (pin "2") (pinfunction "1_2") (pintype "passive"))
      (node (ref "U1") (pin "21") (pinfunction "P17_21") (pintype "output"))
    )
    (net (code "65") (name "Net-(RN2C-1)") (class "Default")
      (node (ref "RN2") (pin "3") (pinfunction "1_3") (pintype "passive"))
      (node (ref "U1") (pin "20") (pinfunction "P18_20") (pintype "output"))
    )
    (net (code "66") (name "Net-(RN2D-1)") (class "Default")
      (node (ref "RN2") (pin "4") (pinfunction "1_4") (pintype "passive"))
      (node (ref "U1") (pin "19") (pinfunction "P19_19") (pintype "output"))
    )
    (net (code "67") (name "Net-(RN3B-1)") (class "Default")
      (node (ref "RN3") (pin "2") (pinfunction "1_2") (pintype "passive"))
      (node (ref "U1") (pin "28") (pinfunction "P13_28") (pintype "output"))
    )
    (net (code "68") (name "Net-(RN3C-1)") (class "Default")
      (node (ref "RN3") (pin "3") (pinfunction "1_3") (pintype "passive"))
      (node (ref "U1") (pin "27") (pinfunction "P14_27") (pintype "output"))
    )
    (net (code "69") (name "Net-(RN3D-1)") (class "Default")
      (node (ref "RN3") (pin "4") (pinfunction "1_4") (pintype "passive"))
      (node (ref "U1") (pin "26") (pinfunction "P15_26") (pintype "output"))
    )
    (net (code "70") (name "Net-(RN4B-1)") (class "Default")
      (node (ref "RN4") (pin "2") (pinfunction "1_2") (pintype "passive"))
      (node (ref "U1") (pin "32") (pinfunction "P9_32") (pintype "output"))
    )
    (net (code "71") (name "Net-(RN4C-1)") (class "Default")
      (node (ref "RN4") (pin "3") (pinfunction "1_3") (pintype "passive"))
      (node (ref "U1") (pin "31") (pinfunction "P10_31") (pintype "output"))
    )
    (net (code "72") (name "Net-(RN4D-1)") (class "Default")
      (node (ref "RN4") (pin "4") (pinfunction "1_4") (pintype "passive"))
      (node (ref "U1") (pin "30") (pinfunction "P11_30") (pintype "output"))
    )
    (net (code "73") (name "Net-(RN5B-1)") (class "Default")
      (node (ref "RN5") (pin "2") (pinfunction "1_2") (pintype "passive"))
      (node (ref "U1") (pin "37") (pinfunction "P5_37") (pintype "output"))
    )
    (net (code "74") (name "Net-(RN5C-1)") (class "Default")
      (node (ref "RN5") (pin "3") (pinfunction "1_3") (pintype "passive"))
      (node (ref "U1") (pin "36") (pinfunction "P6_36") (pintype "output"))
    )
    (net (code "75") (name "Net-(RN5D-1)") (class "Default")
      (node (ref "RN5") (pin "4") (pinfunction "1_4") (pintype "passive"))
      (node (ref "U1") (pin "35") (pinfunction "P7_35") (pintype "output"))
    )
    (net (code "76") (name "Net-(RN6B-1)") (class "Default")
      (node (ref "RN6") (pin "2") (pinfunction "1_2") (pintype "passive"))
      (node (ref "U1") (pin "42") (pinfunction "P1_42") (pintype "output"))
    )
    (net (code "77") (name "Net-(RN6C-1)") (class "Default")
      (node (ref "RN6") (pin "3") (pinfunction "1_3") (pintype "passive"))
      (node (ref "U1") (pin "41") (pinfunction "P2_41") (pintype "output"))
    )
    (net (code "78") (name "Net-(RN6D-1)") (class "Default")
      (node (ref "RN6") (pin "4") (pinfunction "1_4") (pintype "passive"))
      (node (ref "U1") (pin "39") (pinfunction "P3_39") (pintype "output"))
    )
    (net (code "79") (name "Net-(RN7B-1)") (class "Default")
      (node (ref "RN7") (pin "2") (pinfunction "1_2") (pintype "passive"))
      (node (ref "U1") (pin "46") (pinfunction "HS_46") (pintype "output"))
    )
    (net (code "80") (name "Net-(RN7C-1)") (class "Default")
      (node (ref "RN7") (pin "3") (pinfunction "1_3") (pintype "passive"))
      (node (ref "U1") (pin "45") (pinfunction "DE_45") (pintype "input"))
    )
    (net (code "81") (name "Net-(RN7C-2)") (class "Default")
      (node (ref "RN7") (pin "6") (pinfunction "2_6") (pintype "passive"))
      (node (ref "TP1") (pin "TP") (pinfunction "TP_TP") (pintype "input"))
    )
    (net (code "82") (name "Net-(RN8B-1)") (class "Default")
      (node (ref "RN8") (pin "2") (pinfunction "1_2") (pintype "passive"))
      (node (ref "U1") (pin "50") (pinfunction "LRCLK_50") (pintype "input"))
    )
    (net (code "83") (name "Net-(RN8C-1)") (class "Default")
      (node (ref "RN8") (pin "3") (pinfunction "1_3") (pintype "passive"))
      (node (ref "U1") (pin "49") (pinfunction "SCLK/INT2_49") (pintype "input"))
    )
    (net (code "84") (name "Net-(RN8D-1)") (class "Default")
      (node (ref "RN8") (pin "4") (pinfunction "1_4") (pintype "passive"))
      (node (ref "U1") (pin "48") (pinfunction "AP_48") (pintype "output"))
    )
    (net (code "85") (name "Net-(U1-LLC)") (class "Default")
      (node (ref "R2") (pin "1") (pinfunction "1_1") (pintype "passive"))
      (node (ref "U1") (pin "25") (pinfunction "LLC_25") (pintype "input"))
    )
    (net (code "86") (name "Net-(U1-MCLK{slash}INT2)") (class "Default")
      (node (ref "RN8") (pin "1") (pinfunction "1_1") (pintype "passive"))
      (node (ref "U1") (pin "51") (pinfunction "MCLK/INT2_51") (pintype "input"))
    )
    (net (code "87") (name "Net-(U1-P0)") (class "Default")
      (node (ref "RN6") (pin "1") (pinfunction "1_1") (pintype "passive"))
      (node (ref "U1") (pin "43") (pinfunction "P0_43") (pintype "output"))
    )
    (net (code "88") (name "Net-(U1-P4)") (class "Default")
      (node (ref "RN5") (pin "1") (pinfunction "1_1") (pintype "passive"))
      (node (ref "U1") (pin "38") (pinfunction "P4_38") (pintype "output"))
    )
    (net (code "89") (name "Net-(U1-P8)") (class "Default")
      (node (ref "RN4") (pin "1") (pinfunction "1_1") (pintype "passive"))
      (node (ref "U1") (pin "33") (pinfunction "P8_33") (pintype "output"))
    )
    (net (code "90") (name "Net-(U1-P12)") (class "Default")
      (node (ref "RN3") (pin "1") (pinfunction "1_1") (pintype "passive"))
      (node (ref "U1") (pin "29") (pinfunction "P12_29") (pintype "output"))
    )
    (net (code "91") (name "Net-(U1-P16)") (class "Default")
      (node (ref "RN2") (pin "1") (pinfunction "1_1") (pintype "passive"))
      (node (ref "U1") (pin "22") (pinfunction "P16_22") (pintype "output"))
    )
    (net (code "92") (name "Net-(U1-P20)") (class "Default")
      (node (ref "RN1") (pin "1") (pinfunction "1_1") (pintype "passive"))
      (node (ref "U1") (pin "18") (pinfunction "P20_18") (pintype "output"))
    )
    (net (code "93") (name "Net-(U1-RXA_0+)") (class "Default")
      (node (ref "D2") (pin "5") (pinfunction "4_5") (pintype "passive"))
      (node (ref "D2") (pin "6") (pinfunction "4_6") (pintype "passive"))
      (node (ref "K1") (pin "7") (pinfunction "7_7") (pintype "passive"))
      (node (ref "U1") (pin "7") (pinfunction "RXA_0+_7") (pintype "input"))
    )
    (net (code "94") (name "Net-(U1-RXA_0-)") (class "Default")
      (node (ref "D2") (pin "4") (pinfunction "3_4") (pintype "passive"))
      (node (ref "D2") (pin "7") (pinfunction "3_7") (pintype "passive"))
      (node (ref "K1") (pin "9") (pinfunction "9_9") (pintype "passive"))
      (node (ref "U1") (pin "6") (pinfunction "RXA_0-_6") (pintype "input"))
    )
    (net (code "95") (name "Net-(U1-RXA_1+)") (class "Default")
      (node (ref "D1") (pin "2") (pinfunction "2_2") (pintype "passive"))
      (node (ref "D1") (pin "9") (pinfunction "2_9") (pintype "passive"))
      (node (ref "K1") (pin "4") (pinfunction "4_4") (pintype "passive"))
      (node (ref "U1") (pin "10") (pinfunction "RXA_1+_10") (pintype "input"))
    )
    (net (code "96") (name "Net-(U1-RXA_1-)") (class "Default")
      (node (ref "D1") (pin "1") (pinfunction "1_1") (pintype "passive"))
      (node (ref "D1") (pin "10") (pinfunction "1_10") (pintype "passive"))
      (node (ref "K1") (pin "6") (pinfunction "6_6") (pintype "passive"))
      (node (ref "U1") (pin "9") (pinfunction "RXA_1-_9") (pintype "input"))
    )
    (net (code "97") (name "Net-(U1-RXA_2+)") (class "Default")
      (node (ref "D1") (pin "5") (pinfunction "4_5") (pintype "passive"))
      (node (ref "D1") (pin "6") (pinfunction "4_6") (pintype "passive"))
      (node (ref "K1") (pin "1") (pinfunction "1_1") (pintype "passive"))
      (node (ref "U1") (pin "13") (pinfunction "RXA_2+_13") (pintype "input"))
    )
    (net (code "98") (name "Net-(U1-RXA_2-)") (class "Default")
      (node (ref "D1") (pin "4") (pinfunction "3_4") (pintype "passive"))
      (node (ref "D1") (pin "7") (pinfunction "3_7") (pintype "passive"))
      (node (ref "K1") (pin "3") (pinfunction "3_3") (pintype "passive"))
      (node (ref "U1") (pin "12") (pinfunction "RXA_2-_12") (pintype "input"))
    )
    (net (code "99") (name "Net-(U2-EN)") (class "Default")
      (node (ref "C37") (pin "1") (pinfunction "1_1") (pintype "passive"))
      (node (ref "R4") (pin "1") (pinfunction "1_1") (pintype "passive"))
      (node (ref "U2") (pin "3") (pinfunction "EN_3") (pintype "input"))
    )
    (net (code "100") (name "PB2{slash}PWM0") (class "Default")
      (node (ref "CON1") (pin "D-36") (pinfunction "36_D-36") (pintype "passive"))
      (node (ref "R11") (pin "2") (pinfunction "2_2") (pintype "passive"))
      (node (ref "S1") (pin "1") (pinfunction "1_1") (pintype "passive"))
    )
    (net (code "101") (name "PVDD_1V8") (class "Default")
      (node (ref "C36") (pin "1") (pinfunction "1_1") (pintype "passive"))
      (node (ref "C5") (pin "1") (pinfunction "1_1") (pintype "passive"))
      (node (ref "C6") (pin "1") (pinfunction "1_1") (pintype "passive"))
      (node (ref "L6") (pin "1") (pinfunction "1_1") (pintype "passive"))
      (node (ref "U1") (pin "57") (pinfunction "PVDD_57") (pintype "power_in"))
    )
    (net (code "102") (name "SPI2_CLK") (class "Default")
      (node (ref "CON1") (pin "1-35") (pinfunction "35_1-35") (pintype "passive"))
      (node (ref "SV1") (pin "6") (pinfunction "6_6") (pintype "passive"))
    )
    (net (code "103") (name "SPI2_CS0") (class "Default")
      (node (ref "CON1") (pin "1-33") (pinfunction "33_1-33") (pintype "passive"))
      (node (ref "SV1") (pin "8") (pinfunction "8_8") (pintype "passive"))
    )
    (net (code "104") (name "SPI2_MISO") (class "Default")
      (node (ref "CON1") (pin "1-39") (pinfunction "39_1-39") (pintype "passive"))
      (node (ref "SV1") (pin "2") (pinfunction "2_2") (pintype "passive"))
    )
    (net (code "105") (name "SPI2_MOSI") (class "Default")
      (node (ref "CON1") (pin "1-37") (pinfunction "37_1-37") (pintype "passive"))
      (node (ref "SV1") (pin "4") (pinfunction "4_4") (pintype "passive"))
    )
    (net (code "106") (name "TVDD_3V3") (class "Default")
      (node (ref "C10") (pin "1") (pinfunction "1_1") (pintype "passive"))
      (node (ref "C11") (pin "1") (pinfunction "1_1") (pintype "passive"))
      (node (ref "C12") (pin "1") (pinfunction "1_1") (pintype "passive"))
      (node (ref "C13") (pin "1") (pinfunction "1_1") (pintype "passive"))
      (node (ref "C14") (pin "1") (pinfunction "1_1") (pintype "passive"))
      (node (ref "C15") (pin "1") (pinfunction "1_1") (pintype "passive"))
      (node (ref "C33") (pin "1") (pinfunction "1_1") (pintype "passive"))
      (node (ref "L2") (pin "1") (pinfunction "1_1") (pintype "passive"))
      (node (ref "U1") (pin "11") (pinfunction "TVDD_11") (pintype "power_in"))
      (node (ref "U1") (pin "5") (pinfunction "TVDD_2_5") (pintype "power_in"))
      (node (ref "U1") (pin "8") (pinfunction "TVDD_3_8") (pintype "power_in"))
    )
    (net (code "107") (name "TWI2_SCL") (class "Default")
      (node (ref "CON1") (pin "1-32") (pinfunction "32_1-32") (pintype "passive"))
      (node (ref "SV1") (pin "1") (pinfunction "1_1") (pintype "passive"))
    )
    (net (code "108") (name "TWI2_SDA") (class "Default")
      (node (ref "CON1") (pin "1-30") (pinfunction "30_1-30") (pintype "passive"))
      (node (ref "SV1") (pin "3") (pinfunction "3_3") (pintype "passive"))
    )
    (net (code "109") (name "UART0_RX") (class "Default")
      (node (ref "CON1") (pin "1-26") (pinfunction "26_1-26") (pintype "passive"))
      (node (ref "SV1") (pin "7") (pinfunction "7_7") (pintype "passive"))
    )
    (net (code "110") (name "UART0_TX") (class "Default")
      (node (ref "CON1") (pin "1-28") (pinfunction "28_1-28") (pintype "passive"))
      (node (ref "SV1") (pin "5") (pinfunction "5_5") (pintype "passive"))
    )
    (net (code "111") (name "VCC") (class "Default")
      (node (ref "C39") (pin "1") (pinfunction "1_1") (pintype "passive"))
      (node (ref "C40") (pin "+") (pinfunction "+_+") (pintype "passive"))
      (node (ref "CON1") (pin "1-3") (pinfunction "3_1-3") (pintype "passive"))
      (node (ref "CON1") (pin "3-3") (pinfunction "3_3-3") (pintype "passive"))
      (node (ref "CON1") (pin "4-1") (pinfunction "1_4-1") (pintype "passive"))
      (node (ref "CON1") (pin "D-3") (pinfunction "3_D-3") (pintype "passive"))
      (node (ref "D1") (pin "3") (pinfunction "VDD_3") (pintype "power_in"))
      (node (ref "D2") (pin "3") (pinfunction "VDD_3") (pintype "power_in"))
      (node (ref "D3") (pin "3") (pinfunction "VDD_3") (pintype "power_in"))
      (node (ref "L2") (pin "2") (pinfunction "2_2") (pintype "passive"))
      (node (ref "L3") (pin "2") (pinfunction "2_2") (pintype "passive"))
      (node (ref "R10") (pin "1") (pinfunction "1_1") (pintype "passive"))
      (node (ref "R11") (pin "1") (pinfunction "1_1") (pintype "passive"))
      (node (ref "R4") (pin "2") (pinfunction "2_2") (pintype "passive"))
      (node (ref "R5") (pin "2") (pinfunction "2_2") (pintype "passive"))
      (node (ref "R6") (pin "2") (pinfunction "2_2") (pintype "passive"))
      (node (ref "R9") (pin "1") (pinfunction "1_1") (pintype "passive"))
      (node (ref "SV1") (pin "10") (pinfunction "10_10") (pintype "passive"))
      (node (ref "U2") (pin "4") (pinfunction "BIAS_4") (pintype "power_in"))
      (node (ref "U2") (pin "6") (pinfunction "IN_6") (pintype "input"))
    )
    (net (code "112") (name "VDD_1V8") (class "Default")
      (node (ref "C38") (pin "1") (pinfunction "1_1") (pintype "passive"))
      (node (ref "L4") (pin "2") (pinfunction "2_2") (pintype "passive"))
      (node (ref "L5") (pin "2") (pinfunction "2_2") (pintype "passive"))
      (node (ref "L6") (pin "2") (pinfunction "2_2") (pintype "passive"))
      (node (ref "U2") (pin "1") (pinfunction "OUT_1") (pintype "output"))
    )
    (net (code "113") (name "VDD_5V") (class "Default")
      (node (ref "C30") (pin "1") (pinfunction "1_1") (pintype "passive"))
      (node (ref "C31") (pin "1") (pinfunction "1_1") (pintype "passive"))
      (node (ref "L1") (pin "1") (pinfunction "1_1") (pintype "passive"))
      (node (ref "Q1") (pin "1") (pinfunction "G_1") (pintype "passive"))
    )
    (net (code "114") (name "VS_FIELD") (class "Default")
      (node (ref "RN7") (pin "1") (pinfunction "1_1") (pintype "passive"))
      (node (ref "U1") (pin "47") (pinfunction "VS/FIELD/ALSB_47") (pintype "input"))
    )
    (net (code "115") (name "XTALN") (class "Default")
      (node (ref "C2") (pin "1") (pinfunction "1_1") (pintype "passive"))
      (node (ref "R1") (pin "2") (pinfunction "2_2") (pintype "passive"))
      (node (ref "U1") (pin "59") (pinfunction "XTALN_59") (pintype "input"))
      (node (ref "Y1") (pin "P$3") (pinfunction "2_P$3") (pintype "passive"))
    )
    (net (code "116") (name "XTALP") (class "Default")
      (node (ref "C1") (pin "1") (pinfunction "1_1") (pintype "passive"))
      (node (ref "R1") (pin "1") (pinfunction "1_1") (pintype "passive"))
      (node (ref "U1") (pin "58") (pinfunction "XTALP_58") (pintype "input"))
      (node (ref "Y1") (pin "P$1") (pinfunction "1_P$1") (pintype "passive"))
    )
    (net (code "117") (name "unconnected-(CON1A-4-Pad1-4)") (class "Default")
      (node (ref "CON1") (pin "1-4") (pinfunction "4_1-4") (pintype "passive"))
    )
    (net (code "118") (name "unconnected-(CON1A-6-Pad1-6)") (class "Default")
      (node (ref "CON1") (pin "1-6") (pinfunction "6_1-6") (pintype "passive"))
    )
    (net (code "119") (name "unconnected-(CON1A-8-Pad1-8)") (class "Default")
      (node (ref "CON1") (pin "1-8") (pinfunction "8_1-8") (pintype "passive"))
    )
    (net (code "120") (name "unconnected-(CON1A-10-Pad1-10)") (class "Default")
      (node (ref "CON1") (pin "1-10") (pinfunction "10_1-10") (pintype "passive"))
    )
    (net (code "121") (name "unconnected-(CON1A-12-Pad1-12)") (class "Default")
      (node (ref "CON1") (pin "1-12") (pinfunction "12_1-12") (pintype "passive"))
    )
    (net (code "122") (name "unconnected-(CON1A-14-Pad1-14)") (class "Default")
      (node (ref "CON1") (pin "1-14") (pinfunction "14_1-14") (pintype "passive"))
    )
    (net (code "123") (name "unconnected-(CON1A-16-Pad1-16)") (class "Default")
      (node (ref "CON1") (pin "1-16") (pinfunction "16_1-16") (pintype "passive"))
    )
    (net (code "124") (name "unconnected-(CON1A-18-Pad1-18)") (class "Default")
      (node (ref "CON1") (pin "1-18") (pinfunction "18_1-18") (pintype "passive"))
    )
    (net (code "125") (name "unconnected-(CON1A-20-Pad1-20)") (class "Default")
      (node (ref "CON1") (pin "1-20") (pinfunction "20_1-20") (pintype "passive"))
    )
    (net (code "126") (name "unconnected-(CON1A-22-Pad1-22)") (class "Default")
      (node (ref "CON1") (pin "1-22") (pinfunction "22_1-22") (pintype "passive"))
    )
    (net (code "127") (name "unconnected-(CON1A-24-Pad1-24)") (class "Default")
      (node (ref "CON1") (pin "1-24") (pinfunction "24_1-24") (pintype "passive"))
    )
    (net (code "128") (name "unconnected-(CON1A-29-Pad1-29)") (class "Default")
      (node (ref "CON1") (pin "1-29") (pinfunction "29_1-29") (pintype "passive"))
    )
    (net (code "129") (name "unconnected-(CON1A-31-Pad1-31)") (class "Default")
      (node (ref "CON1") (pin "1-31") (pinfunction "31_1-31") (pintype "passive"))
    )
    (net (code "130") (name "unconnected-(CON1A-40-Pad1-40)") (class "Default")
      (node (ref "CON1") (pin "1-40") (pinfunction "40_1-40") (pintype "passive"))
    )
    (net (code "131") (name "unconnected-(CON1B-1-Pad3-1)") (class "Default")
      (node (ref "CON1") (pin "3-1") (pinfunction "1_3-1") (pintype "passive"))
    )
    (net (code "132") (name "unconnected-(CON1B-5-Pad3-5)") (class "Default")
      (node (ref "CON1") (pin "3-5") (pinfunction "5_3-5") (pintype "passive"))
    )
    (net (code "133") (name "unconnected-(CON1B-6-Pad3-6)") (class "Default")
      (node (ref "CON1") (pin "3-6") (pinfunction "6_3-6") (pintype "passive"))
    )
    (net (code "134") (name "unconnected-(CON1B-8-Pad3-8)") (class "Default")
      (node (ref "CON1") (pin "3-8") (pinfunction "8_3-8") (pintype "passive"))
    )
    (net (code "135") (name "unconnected-(CON1B-9-Pad3-9)") (class "Default")
      (node (ref "CON1") (pin "3-9") (pinfunction "9_3-9") (pintype "passive"))
    )
    (net (code "136") (name "unconnected-(CON1B-16-Pad3-16)") (class "Default")
      (node (ref "CON1") (pin "3-16") (pinfunction "16_3-16") (pintype "passive"))
    )
    (net (code "137") (name "unconnected-(CON1B-18-Pad3-18)") (class "Default")
      (node (ref "CON1") (pin "3-18") (pinfunction "18_3-18") (pintype "passive"))
    )
    (net (code "138") (name "unconnected-(CON1B-20-Pad3-20)") (class "Default")
      (node (ref "CON1") (pin "3-20") (pinfunction "20_3-20") (pintype "passive"))
    )
    (net (code "139") (name "unconnected-(CON1B-24-Pad3-24)") (class "Default")
      (node (ref "CON1") (pin "3-24") (pinfunction "24_3-24") (pintype "passive"))
    )
    (net (code "140") (name "unconnected-(CON1B-26-Pad3-26)") (class "Default")
      (node (ref "CON1") (pin "3-26") (pinfunction "26_3-26") (pintype "passive"))
    )
    (net (code "141") (name "unconnected-(CON1B-28-Pad3-28)") (class "Default")
      (node (ref "CON1") (pin "3-28") (pinfunction "28_3-28") (pintype "passive"))
    )
    (net (code "142") (name "unconnected-(CON1B-30-Pad3-30)") (class "Default")
      (node (ref "CON1") (pin "3-30") (pinfunction "30_3-30") (pintype "passive"))
    )
    (net (code "143") (name "unconnected-(CON1B-32-Pad3-32)") (class "Default")
      (node (ref "CON1") (pin "3-32") (pinfunction "32_3-32") (pintype "passive"))
    )
    (net (code "144") (name "unconnected-(CON1B-34-Pad3-34)") (class "Default")
      (node (ref "CON1") (pin "3-34") (pinfunction "34_3-34") (pintype "passive"))
    )
    (net (code "145") (name "unconnected-(CON1B-38-Pad3-38)") (class "Default")
      (node (ref "CON1") (pin "3-38") (pinfunction "38_3-38") (pintype "passive"))
    )
    (net (code "146") (name "unconnected-(CON1B-40-Pad3-40)") (class "Default")
      (node (ref "CON1") (pin "3-40") (pinfunction "40_3-40") (pintype "passive"))
    )
    (net (code "147") (name "unconnected-(CON1C-3-Pad4-3)") (class "Default")
      (node (ref "CON1") (pin "4-3") (pinfunction "3_4-3") (pintype "passive"))
    )
    (net (code "148") (name "unconnected-(CON1C-4-Pad4-4)") (class "Default")
      (node (ref "CON1") (pin "4-4") (pinfunction "4_4-4") (pintype "passive"))
    )
    (net (code "149") (name "unconnected-(CON1C-5-Pad4-5)") (class "Default")
      (node (ref "CON1") (pin "4-5") (pinfunction "5_4-5") (pintype "passive"))
    )
    (net (code "150") (name "unconnected-(CON1C-6-Pad4-6)") (class "Default")
      (node (ref "CON1") (pin "4-6") (pinfunction "6_4-6") (pintype "passive"))
    )
    (net (code "151") (name "unconnected-(CON1C-7-Pad4-7)") (class "Default")
      (node (ref "CON1") (pin "4-7") (pinfunction "7_4-7") (pintype "passive"))
    )
    (net (code "152") (name "unconnected-(CON1C-8-Pad4-8)") (class "Default")
      (node (ref "CON1") (pin "4-8") (pinfunction "8_4-8") (pintype "passive"))
    )
    (net (code "153") (name "unconnected-(CON1C-9-Pad4-9)") (class "Default")
      (node (ref "CON1") (pin "4-9") (pinfunction "9_4-9") (pintype "passive"))
    )
    (net (code "154") (name "unconnected-(CON1C-10-Pad4-10)") (class "Default")
      (node (ref "CON1") (pin "4-10") (pinfunction "10_4-10") (pintype "passive"))
    )
    (net (code "155") (name "unconnected-(CON1C-11-Pad4-11)") (class "Default")
      (node (ref "CON1") (pin "4-11") (pinfunction "11_4-11") (pintype "passive"))
    )
    (net (code "156") (name "unconnected-(CON1C-16-Pad4-16)") (class "Default")
      (node (ref "CON1") (pin "4-16") (pinfunction "16_4-16") (pintype "passive"))
    )
    (net (code "157") (name "unconnected-(CON1C-17-Pad4-17)") (class "Default")
      (node (ref "CON1") (pin "4-17") (pinfunction "17_4-17") (pintype "passive"))
    )
    (net (code "158") (name "unconnected-(CON1C-18-Pad4-18)") (class "Default")
      (node (ref "CON1") (pin "4-18") (pinfunction "18_4-18") (pintype "passive"))
    )
    (net (code "159") (name "unconnected-(CON1C-19-Pad4-19)") (class "Default")
      (node (ref "CON1") (pin "4-19") (pinfunction "19_4-19") (pintype "passive"))
    )
    (net (code "160") (name "unconnected-(CON1C-20-Pad4-20)") (class "Default")
      (node (ref "CON1") (pin "4-20") (pinfunction "20_4-20") (pintype "passive"))
    )
    (net (code "161") (name "unconnected-(CON1D-1-PadD-1)") (class "Default")
      (node (ref "CON1") (pin "D-1") (pinfunction "1_D-1") (pintype "passive"))
    )
    (net (code "162") (name "unconnected-(CON1D-5-PadD-5)") (class "Default")
      (node (ref "CON1") (pin "D-5") (pinfunction "5_D-5") (pintype "passive"))
    )
    (net (code "163") (name "unconnected-(CON1D-6-PadD-6)") (class "Default")
      (node (ref "CON1") (pin "D-6") (pinfunction "6_D-6") (pintype "passive"))
    )
    (net (code "164") (name "unconnected-(CON1D-7-PadD-7)") (class "Default")
      (node (ref "CON1") (pin "D-7") (pinfunction "7_D-7") (pintype "passive"))
    )
    (net (code "165") (name "unconnected-(CON1D-8-PadD-8)") (class "Default")
      (node (ref "CON1") (pin "D-8") (pinfunction "8_D-8") (pintype "passive"))
    )
    (net (code "166") (name "unconnected-(CON1D-9-PadD-9)") (class "Default")
      (node (ref "CON1") (pin "D-9") (pinfunction "9_D-9") (pintype "passive"))
    )
    (net (code "167") (name "unconnected-(CON1D-10-PadD-10)") (class "Default")
      (node (ref "CON1") (pin "D-10") (pinfunction "10_D-10") (pintype "passive"))
    )
    (net (code "168") (name "unconnected-(CON1D-11-PadD-11)") (class "Default")
      (node (ref "CON1") (pin "D-11") (pinfunction "11_D-11") (pintype "passive"))
    )
    (net (code "169") (name "unconnected-(CON1D-12-PadD-12)") (class "Default")
      (node (ref "CON1") (pin "D-12") (pinfunction "12_D-12") (pintype "passive"))
    )
    (net (code "170") (name "unconnected-(CON1D-13-PadD-13)") (class "Default")
      (node (ref "CON1") (pin "D-13") (pinfunction "13_D-13") (pintype "passive"))
    )
    (net (code "171") (name "unconnected-(CON1D-14-PadD-14)") (class "Default")
      (node (ref "CON1") (pin "D-14") (pinfunction "14_D-14") (pintype "passive"))
    )
    (net (code "172") (name "unconnected-(CON1D-15-PadD-15)") (class "Default")
      (node (ref "CON1") (pin "D-15") (pinfunction "15_D-15") (pintype "passive"))
    )
    (net (code "173") (name "unconnected-(CON1D-16-PadD-16)") (class "Default")
      (node (ref "CON1") (pin "D-16") (pinfunction "16_D-16") (pintype "passive"))
    )
    (net (code "174") (name "unconnected-(CON1D-17-PadD-17)") (class "Default")
      (node (ref "CON1") (pin "D-17") (pinfunction "17_D-17") (pintype "passive"))
    )
    (net (code "175") (name "unconnected-(CON1D-18-PadD-18)") (class "Default")
      (node (ref "CON1") (pin "D-18") (pinfunction "18_D-18") (pintype "passive"))
    )
    (net (code "176") (name "unconnected-(CON1D-19-PadD-19)") (class "Default")
      (node (ref "CON1") (pin "D-19") (pinfunction "19_D-19") (pintype "passive"))
    )
    (net (code "177") (name "unconnected-(CON1D-20-PadD-20)") (class "Default")
      (node (ref "CON1") (pin "D-20") (pinfunction "20_D-20") (pintype "passive"))
    )
    (net (code "178") (name "unconnected-(CON1D-21-PadD-21)") (class "Default")
      (node (ref "CON1") (pin "D-21") (pinfunction "21_D-21") (pintype "passive"))
    )
    (net (code "179") (name "unconnected-(CON1D-22-PadD-22)") (class "Default")
      (node (ref "CON1") (pin "D-22") (pinfunction "22_D-22") (pintype "passive"))
    )
    (net (code "180") (name "unconnected-(CON1D-23-PadD-23)") (class "Default")
      (node (ref "CON1") (pin "D-23") (pinfunction "23_D-23") (pintype "passive"))
    )
    (net (code "181") (name "unconnected-(CON1D-24-PadD-24)") (class "Default")
      (node (ref "CON1") (pin "D-24") (pinfunction "24_D-24") (pintype "passive"))
    )
    (net (code "182") (name "unconnected-(CON1D-25-PadD-25)") (class "Default")
      (node (ref "CON1") (pin "D-25") (pinfunction "25_D-25") (pintype "passive"))
    )
    (net (code "183") (name "unconnected-(CON1D-26-PadD-26)") (class "Default")
      (node (ref "CON1") (pin "D-26") (pinfunction "26_D-26") (pintype "passive"))
    )
    (net (code "184") (name "unconnected-(CON1D-27-PadD-27)") (class "Default")
      (node (ref "CON1") (pin "D-27") (pinfunction "27_D-27") (pintype "passive"))
    )
    (net (code "185") (name "unconnected-(CON1D-28-PadD-28)") (class "Default")
      (node (ref "CON1") (pin "D-28") (pinfunction "28_D-28") (pintype "passive"))
    )
    (net (code "186") (name "unconnected-(CON1D-29-PadD-29)") (class "Default")
      (node (ref "CON1") (pin "D-29") (pinfunction "29_D-29") (pintype "passive"))
    )
    (net (code "187") (name "unconnected-(CON1D-30-PadD-30)") (class "Default")
      (node (ref "CON1") (pin "D-30") (pinfunction "30_D-30") (pintype "passive"))
    )
    (net (code "188") (name "unconnected-(CON1D-31-PadD-31)") (class "Default")
      (node (ref "CON1") (pin "D-31") (pinfunction "31_D-31") (pintype "passive"))
    )
    (net (code "189") (name "unconnected-(CON1D-32-PadD-32)") (class "Default")
      (node (ref "CON1") (pin "D-32") (pinfunction "32_D-32") (pintype "passive"))
    )
    (net (code "190") (name "unconnected-(CON1D-33-PadD-33)") (class "Default")
      (node (ref "CON1") (pin "D-33") (pinfunction "33_D-33") (pintype "passive"))
    )
    (net (code "191") (name "unconnected-(CON1D-34-PadD-34)") (class "Default")
      (node (ref "CON1") (pin "D-34") (pinfunction "34_D-34") (pintype "passive"))
    )
    (net (code "192") (name "unconnected-(CON1D-37-PadD-37)") (class "Default")
      (node (ref "CON1") (pin "D-37") (pinfunction "37_D-37") (pintype "passive"))
    )
    (net (code "193") (name "unconnected-(CON1D-38-PadD-38)") (class "Default")
      (node (ref "CON1") (pin "D-38") (pinfunction "38_D-38") (pintype "passive"))
    )
    (net (code "194") (name "unconnected-(CON1D-39-PadD-39)") (class "Default")
      (node (ref "CON1") (pin "D-39") (pinfunction "39_D-39") (pintype "passive"))
    )
    (net (code "195") (name "unconnected-(CON1D-40-PadD-40)") (class "Default")
      (node (ref "CON1") (pin "D-40") (pinfunction "40_D-40") (pintype "passive"))
    )
    (net (code "196") (name "unconnected-(K1-Pad14)") (class "Default")
      (node (ref "K1") (pin "14") (pinfunction "14_14") (pintype "passive"))
    )
    (net (code "197") (name "unconnected-(RN7D-1-Pad4)") (class "Default")
      (node (ref "RN7") (pin "4") (pinfunction "1_4") (pintype "passive"))
    )
    (net (code "198") (name "unconnected-(RN7D-2-Pad5)") (class "Default")
      (node (ref "RN7") (pin "5") (pinfunction "2_5") (pintype "passive"))
    )
    (net (code "199") (name "unconnected-(U2-NC-Pad2)") (class "Default")
      (node (ref "U2") (pin "2") (pinfunction "NC_2") (pintype "no_connect"))
    )
  )
)
